# r4_4.net
KiCad netlist of a schematic drawn in EAGLE
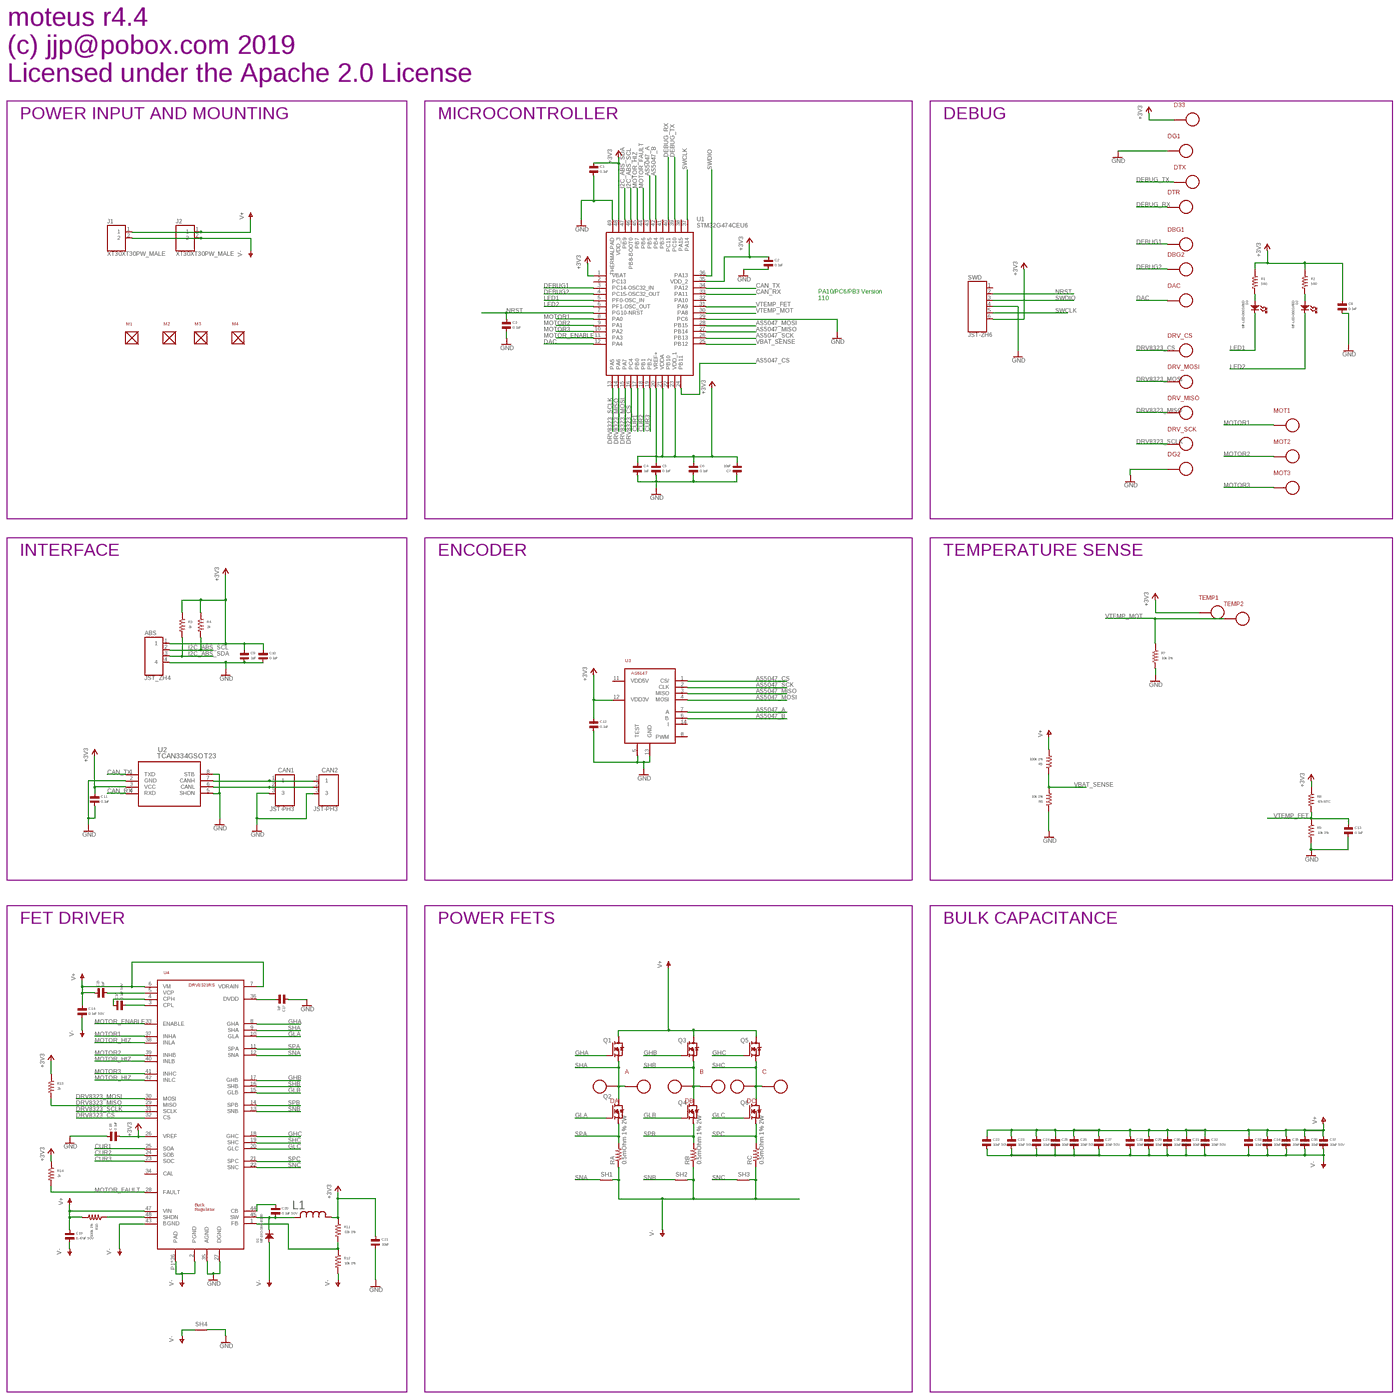
[diagram p0: schematic, sheet 1, overview]
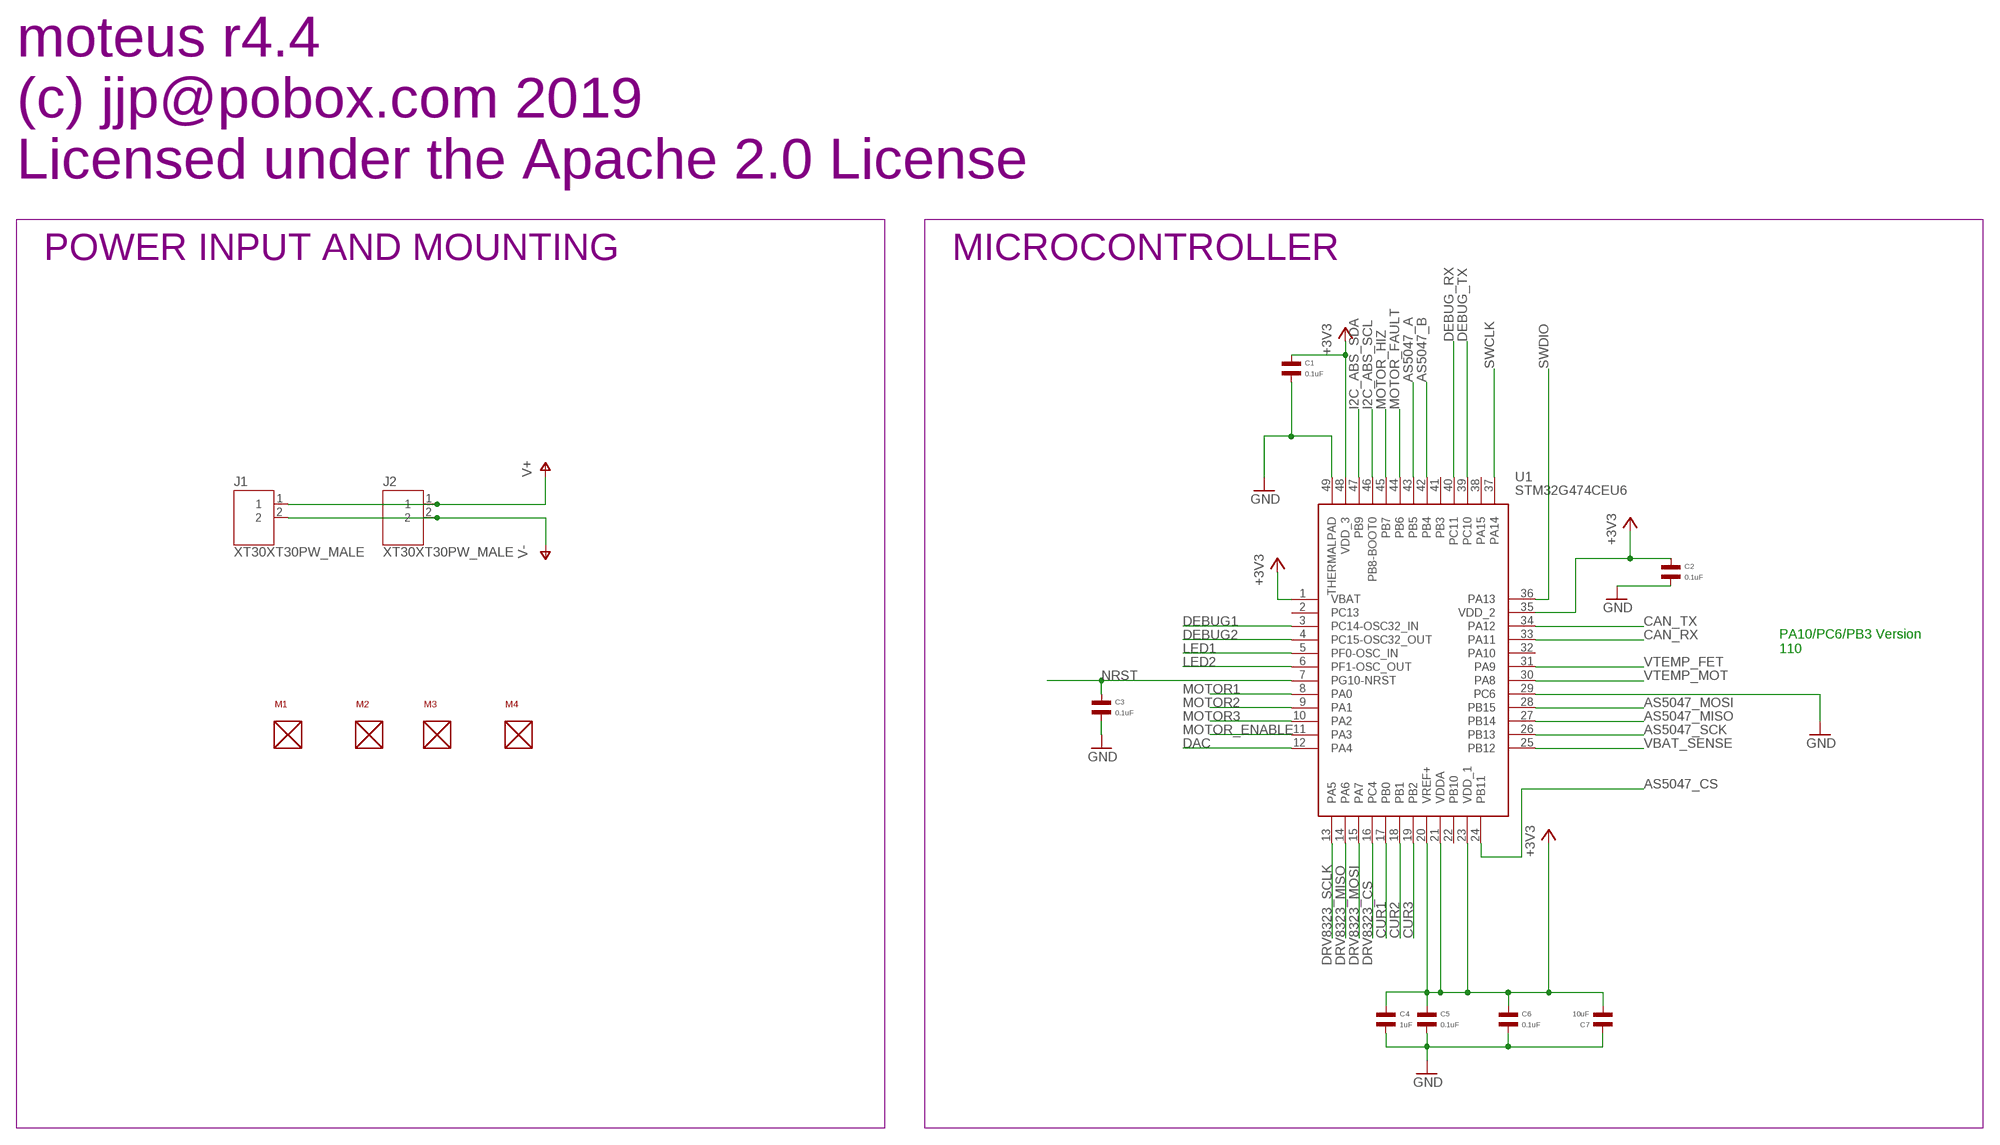
[diagram p1: schematic, sheet 1, part 1 of 4]
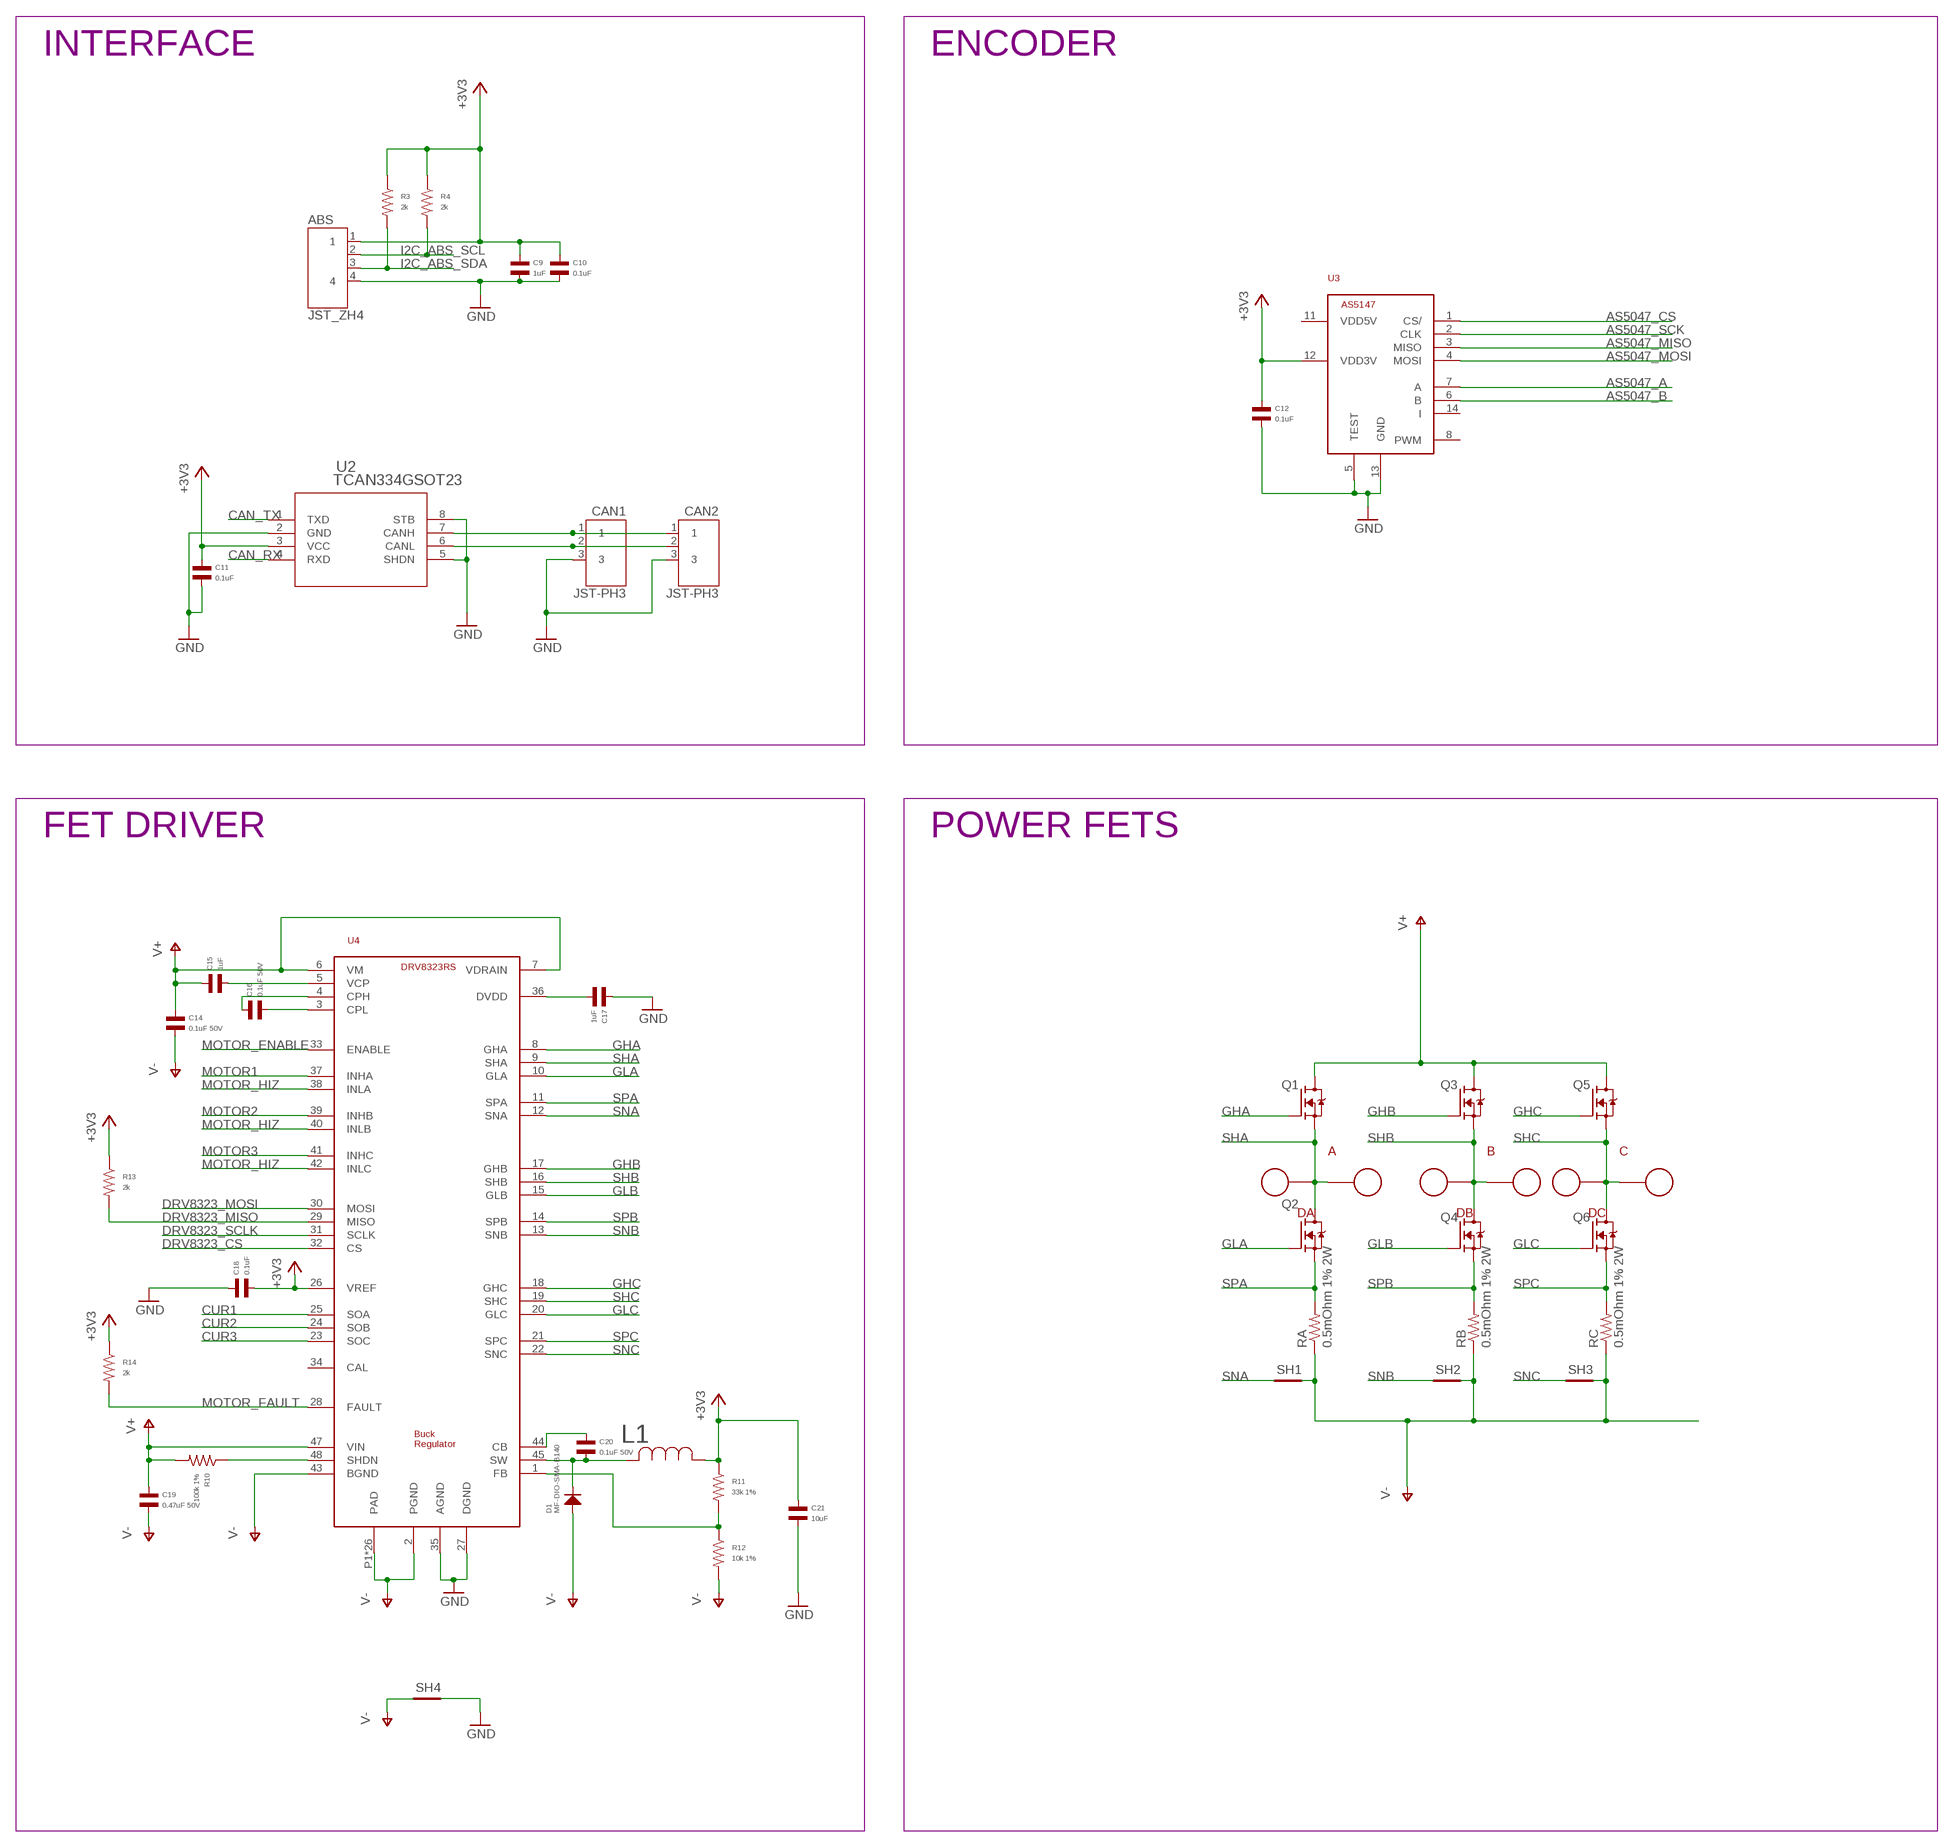
[diagram p2: schematic, sheet 1, part 2 of 4]
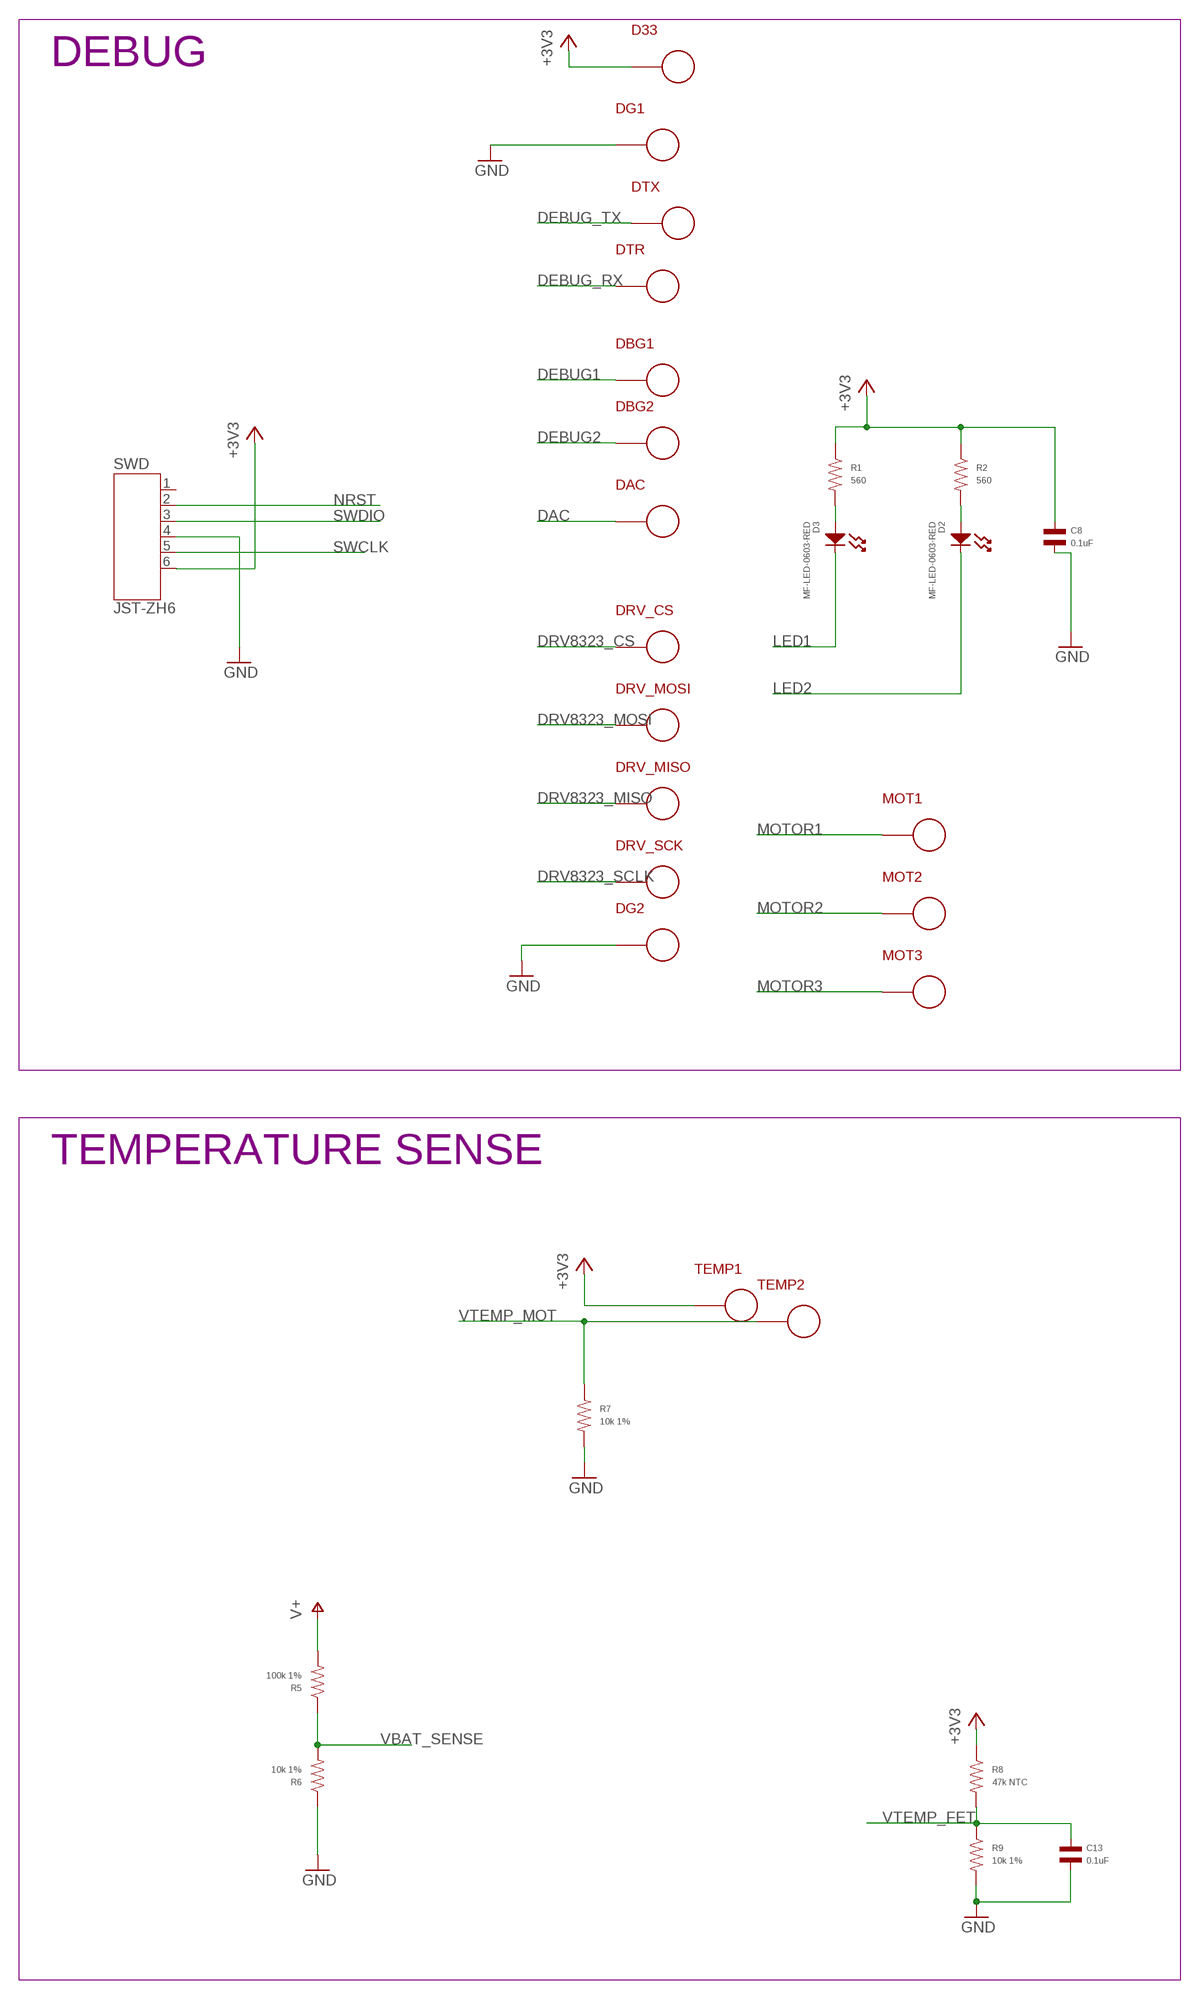
[diagram p3: schematic, sheet 1, part 3 of 4]
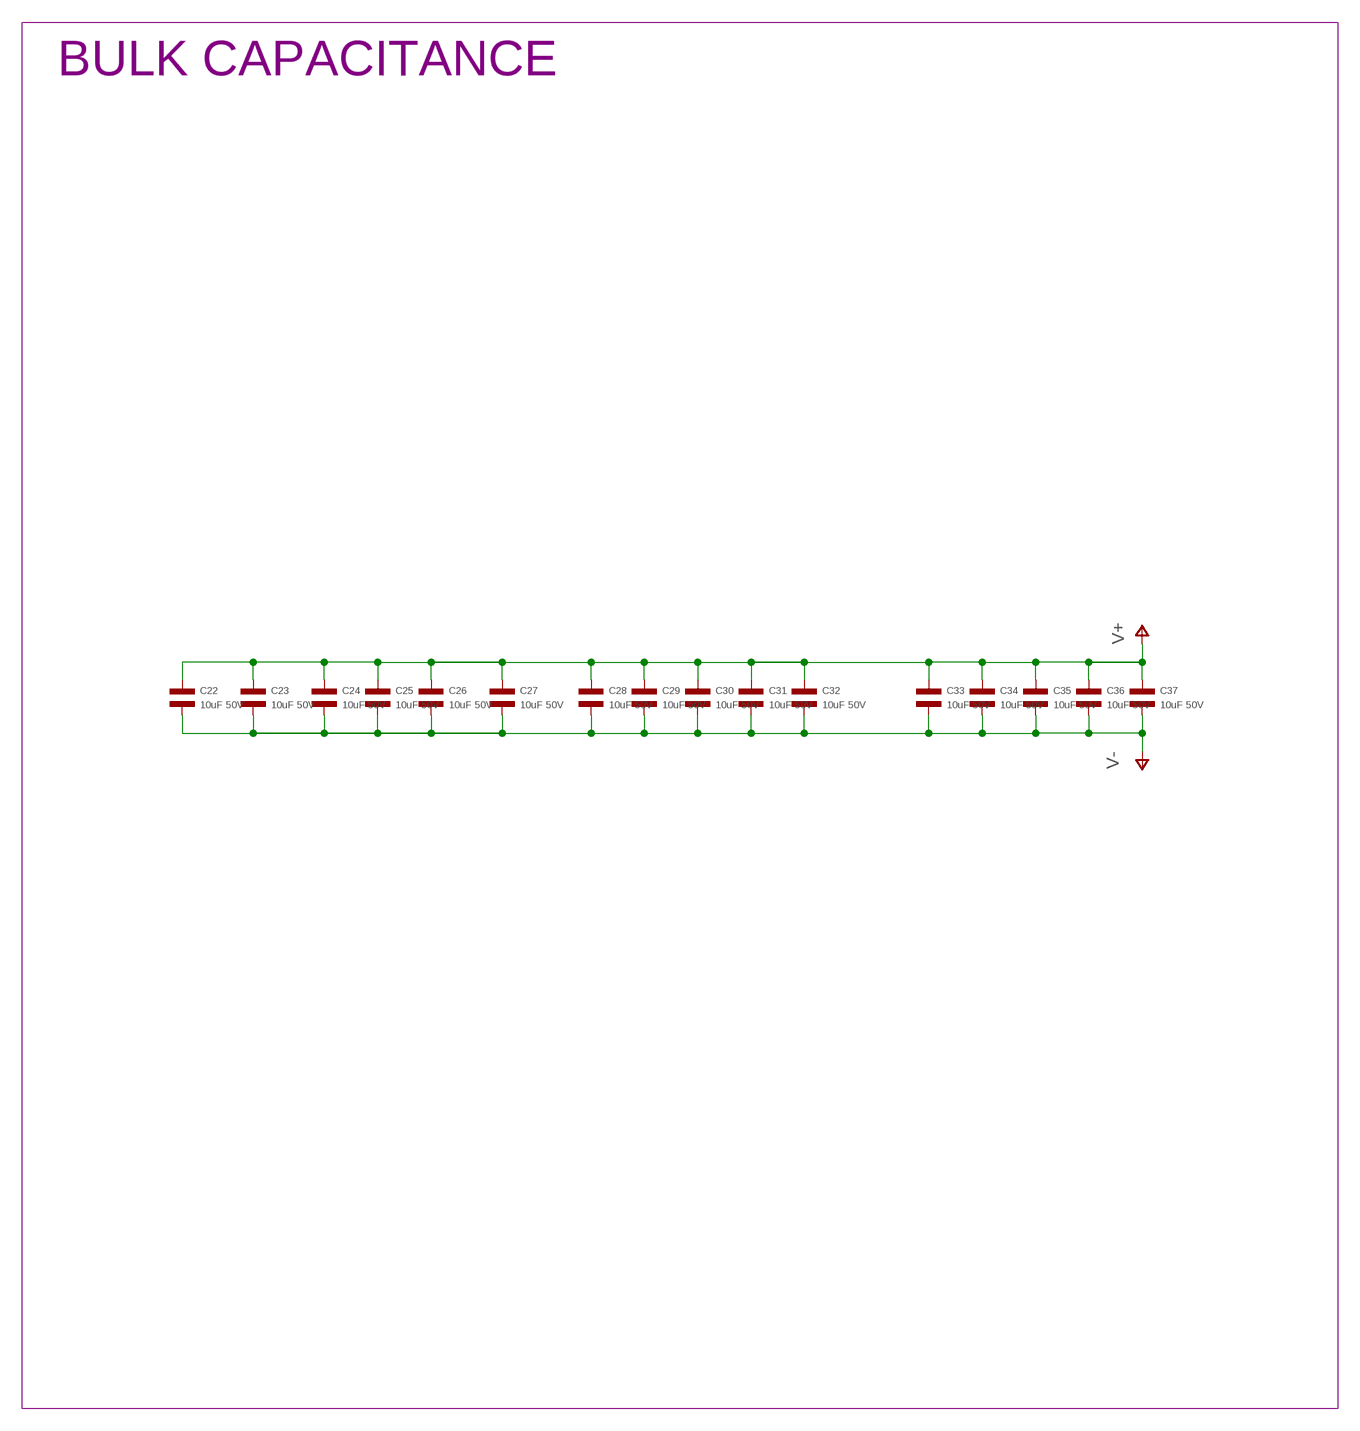
[diagram p4: schematic, sheet 1, part 4 of 4]

(export (version "E")
  (design (tool "Eeschema 10.0.6"))
  (components
    (comp (ref "A")
      (value "PAD")
      (footprint "eagle-import:18AWG_PAD")
      (libsource (lib "eagle-import") (part "PAD"))
    )
    (comp (ref "ABS")
      (value "JST_ZH4")
      (footprint "eagle-import:JST_S4B-ZR-SM4A-TF(LF)(SN)")
      (fields (field (name "MF") "JST") (field (name "MPN") "S4B-ZR-SM4A-TF(LF)(SN)"))
      (libsource (lib "eagle-import") (part "JST_ZH4"))
    )
    (comp (ref "B")
      (value "PAD")
      (footprint "eagle-import:18AWG_PAD")
      (libsource (lib "eagle-import") (part "PAD"))
    )
    (comp (ref "C")
      (value "PAD")
      (footprint "eagle-import:18AWG_PAD")
      (libsource (lib "eagle-import") (part "PAD"))
    )
    (comp (ref "C1")
      (value "0.1uF")
      (footprint "eagle-import:C0402")
      (fields (field (name "HOUSEPART") "YES") (field (name "MPN") "MF-CAP-0402-0.1uF"))
      (libsource (lib "eagle-import") (part "CAPACITOR_NP_0402"))
    )
    (comp (ref "C2")
      (value "0.1uF")
      (footprint "eagle-import:C0402")
      (fields (field (name "HOUSEPART") "YES") (field (name "MPN") "MF-CAP-0402-0.1uF"))
      (libsource (lib "eagle-import") (part "CAPACITOR_NP_0402"))
    )
    (comp (ref "C3")
      (value "0.1uF")
      (footprint "eagle-import:C0402")
      (fields (field (name "HOUSEPART") "YES") (field (name "MPN") "MF-CAP-0402-0.1uF"))
      (libsource (lib "eagle-import") (part "CAPACITOR_NP_0402"))
    )
    (comp (ref "C4")
      (value "1uF")
      (footprint "eagle-import:C0402")
      (fields (field (name "HOUSEPART") "YES") (field (name "MPN") "MF-CAP-0402-1uF"))
      (libsource (lib "eagle-import") (part "CAPACITOR_NP_0402"))
    )
    (comp (ref "C5")
      (value "0.1uF")
      (footprint "eagle-import:C0402")
      (fields (field (name "HOUSEPART") "YES") (field (name "MPN") "MF-CAP-0402-0.1uF"))
      (libsource (lib "eagle-import") (part "CAPACITOR_NP_0402"))
    )
    (comp (ref "C6")
      (value "0.1uF")
      (footprint "eagle-import:C0402")
      (fields (field (name "HOUSEPART") "YES") (field (name "MPN") "MF-CAP-0402-0.1uF"))
      (libsource (lib "eagle-import") (part "CAPACITOR_NP_0402"))
    )
    (comp (ref "C7")
      (value "10uF")
      (footprint "eagle-import:C1206")
      (fields (field (name "HOUSEPART") "YES") (field (name "MPN") "MF-CAP-1206-10uF"))
      (libsource (lib "eagle-import") (part "CAPACITOR_NP_1206"))
    )
    (comp (ref "C8")
      (value "0.1uF")
      (footprint "eagle-import:C0402")
      (fields (field (name "HOUSEPART") "YES") (field (name "MPN") "MF-CAP-0402-0.1uF"))
      (libsource (lib "eagle-import") (part "CAPACITOR_NP_0402"))
    )
    (comp (ref "C9")
      (value "1uF")
      (footprint "eagle-import:C0402")
      (fields (field (name "HOUSEPART") "YES") (field (name "MPN") "MF-CAP-0402-1uF"))
      (libsource (lib "eagle-import") (part "CAPACITOR_NP_0402"))
    )
    (comp (ref "C10")
      (value "0.1uF")
      (footprint "eagle-import:C0402")
      (fields (field (name "HOUSEPART") "YES") (field (name "MPN") "MF-CAP-0402-0.1uF"))
      (libsource (lib "eagle-import") (part "CAPACITOR_NP_0402"))
    )
    (comp (ref "C11")
      (value "0.1uF")
      (footprint "eagle-import:C0402")
      (fields (field (name "HOUSEPART") "YES") (field (name "MPN") "MF-CAP-0402-0.1uF"))
      (libsource (lib "eagle-import") (part "CAPACITOR_NP_0402"))
    )
    (comp (ref "C12")
      (value "0.1uF")
      (footprint "eagle-import:C0402")
      (fields (field (name "HOUSEPART") "YES") (field (name "MPN") "MF-CAP-0402-0.1uF"))
      (libsource (lib "eagle-import") (part "CAPACITOR_NP_0402"))
    )
    (comp (ref "C13")
      (value "0.1uF")
      (footprint "eagle-import:C0402")
      (fields (field (name "HOUSEPART") "YES") (field (name "MPN") "MF-CAP-0402-0.1uF"))
      (libsource (lib "eagle-import") (part "CAPACITOR_NP_0402"))
    )
    (comp (ref "C14")
      (value "0.1uF 50V")
      (footprint "eagle-import:C0402")
      (fields (field (name "MF") "TDK") (field (name "MPN") "CGA2B3X7R1H104K050BB"))
      (libsource (lib "eagle-import") (part "CAPACITOR_NP_0402"))
    )
    (comp (ref "C15")
      (value "1uF")
      (footprint "eagle-import:C0402")
      (fields (field (name "HOUSEPART") "YES") (field (name "MPN") "MF-CAP-0402-1uF"))
      (libsource (lib "eagle-import") (part "CAPACITOR_NP_0402"))
    )
    (comp (ref "C16")
      (value "0.1uF 50V")
      (footprint "eagle-import:C0402")
      (fields (field (name "MF") "TDK") (field (name "MPN") "CGA2B3X7R1H104K050BB"))
      (libsource (lib "eagle-import") (part "CAPACITOR_NP_0402"))
    )
    (comp (ref "C17")
      (value "1uF")
      (footprint "eagle-import:C0402")
      (fields (field (name "HOUSEPART") "YES") (field (name "MPN") "MF-CAP-0402-1uF"))
      (libsource (lib "eagle-import") (part "CAPACITOR_NP_0402"))
    )
    (comp (ref "C18")
      (value "0.1uF")
      (footprint "eagle-import:C0402")
      (fields (field (name "HOUSEPART") "YES") (field (name "MPN") "MF-CAP-0402-0.1uF"))
      (libsource (lib "eagle-import") (part "CAPACITOR_NP_0402"))
    )
    (comp (ref "C19")
      (value "0.47uF 50V")
      (footprint "eagle-import:C0402")
      (fields (field (name "MF") "Taiyo Yuden") (field (name "MPN") "UMK105ABJ474KV-F"))
      (libsource (lib "eagle-import") (part "CAPACITOR_NP_0402"))
    )
    (comp (ref "C20")
      (value "0.1uF 50V")
      (footprint "eagle-import:C0402")
      (fields (field (name "MF") "TDK") (field (name "MPN") "CGA2B3X7R1H104K050BB"))
      (libsource (lib "eagle-import") (part "CAPACITOR_NP_0402"))
    )
    (comp (ref "C21")
      (value "10uF")
      (footprint "eagle-import:C1206")
      (fields (field (name "HOUSEPART") "YES") (field (name "MPN") "MF-CAP-1206-10uF"))
      (libsource (lib "eagle-import") (part "CAPACITOR_NP_1206"))
    )
    (comp (ref "C22")
      (value "10uF 50V")
      (footprint "eagle-import:C1206")
      (fields (field (name "MF") "TDK") (field (name "MPN") "C3216X7R1H106K160AE"))
      (libsource (lib "eagle-import") (part "CAPACITOR_NP_1206"))
    )
    (comp (ref "C23")
      (value "10uF 50V")
      (footprint "eagle-import:C1206")
      (fields (field (name "MF") "TDK") (field (name "MPN") "C3216X7R1H106K160AE"))
      (libsource (lib "eagle-import") (part "CAPACITOR_NP_1206"))
    )
    (comp (ref "C24")
      (value "10uF 50V")
      (footprint "eagle-import:C1206")
      (fields (field (name "MF") "TDK") (field (name "MPN") "C3216X7R1H106K160AE"))
      (libsource (lib "eagle-import") (part "CAPACITOR_NP_1206"))
    )
    (comp (ref "C25")
      (value "10uF 50V")
      (footprint "eagle-import:C1206")
      (fields (field (name "MF") "TDK") (field (name "MPN") "C3216X7R1H106K160AE"))
      (libsource (lib "eagle-import") (part "CAPACITOR_NP_1206"))
    )
    (comp (ref "C26")
      (value "10uF 50V")
      (footprint "eagle-import:C1206")
      (fields (field (name "MF") "TDK") (field (name "MPN") "C3216X7R1H106K160AE"))
      (libsource (lib "eagle-import") (part "CAPACITOR_NP_1206"))
    )
    (comp (ref "C27")
      (value "10uF 50V")
      (footprint "eagle-import:C1206")
      (fields (field (name "MF") "TDK") (field (name "MPN") "C3216X7R1H106K160AE"))
      (libsource (lib "eagle-import") (part "CAPACITOR_NP_1206"))
    )
    (comp (ref "C28")
      (value "10uF 50V")
      (footprint "eagle-import:C1206")
      (fields (field (name "MF") "TDK") (field (name "MPN") "C3216X7R1H106K160AE"))
      (libsource (lib "eagle-import") (part "CAPACITOR_NP_1206"))
    )
    (comp (ref "C29")
      (value "10uF 50V")
      (footprint "eagle-import:C1206")
      (fields (field (name "MF") "TDK") (field (name "MPN") "C3216X7R1H106K160AE"))
      (libsource (lib "eagle-import") (part "CAPACITOR_NP_1206"))
    )
    (comp (ref "C30")
      (value "10uF 50V")
      (footprint "eagle-import:C1206")
      (fields (field (name "MF") "TDK") (field (name "MPN") "C3216X7R1H106K160AE"))
      (libsource (lib "eagle-import") (part "CAPACITOR_NP_1206"))
    )
    (comp (ref "C31")
      (value "10uF 50V")
      (footprint "eagle-import:C1206")
      (fields (field (name "MF") "TDK") (field (name "MPN") "C3216X7R1H106K160AE"))
      (libsource (lib "eagle-import") (part "CAPACITOR_NP_1206"))
    )
    (comp (ref "C32")
      (value "10uF 50V")
      (footprint "eagle-import:C1206")
      (fields (field (name "MF") "TDK") (field (name "MPN") "C3216X7R1H106K160AE"))
      (libsource (lib "eagle-import") (part "CAPACITOR_NP_1206"))
    )
    (comp (ref "C33")
      (value "10uF 50V")
      (footprint "eagle-import:C1206")
      (fields (field (name "MF") "TDK") (field (name "MPN") "C3216X7R1H106K160AE"))
      (libsource (lib "eagle-import") (part "CAPACITOR_NP_1206"))
    )
    (comp (ref "C34")
      (value "10uF 50V")
      (footprint "eagle-import:C1206")
      (fields (field (name "MF") "TDK") (field (name "MPN") "C3216X7R1H106K160AE"))
      (libsource (lib "eagle-import") (part "CAPACITOR_NP_1206"))
    )
    (comp (ref "C35")
      (value "10uF 50V")
      (footprint "eagle-import:C1206")
      (fields (field (name "MF") "TDK") (field (name "MPN") "C3216X7R1H106K160AE"))
      (libsource (lib "eagle-import") (part "CAPACITOR_NP_1206"))
    )
    (comp (ref "C36")
      (value "10uF 50V")
      (footprint "eagle-import:C1206")
      (fields (field (name "MF") "TDK") (field (name "MPN") "C3216X7R1H106K160AE"))
      (libsource (lib "eagle-import") (part "CAPACITOR_NP_1206"))
    )
    (comp (ref "C37")
      (value "10uF 50V")
      (footprint "eagle-import:C1206")
      (fields (field (name "MF") "TDK") (field (name "MPN") "C3216X7R1H106K160AE"))
      (libsource (lib "eagle-import") (part "CAPACITOR_NP_1206"))
    )
    (comp (ref "CAN1")
      (value "JST-PH3")
      (footprint "eagle-import:JST_S3B-PH-SM4-TB(LF)(SN)")
      (fields (field (name "MF") "JST") (field (name "MPN") "S3B-PH-SM4-TB(LF)(SN)"))
      (libsource (lib "eagle-import") (part "JST-PH3"))
    )
    (comp (ref "CAN2")
      (value "JST-PH3")
      (footprint "eagle-import:JST_S3B-PH-SM4-TB(LF)(SN)")
      (fields (field (name "MF") "JST") (field (name "MPN") "S3B-PH-SM4-TB(LF)(SN)"))
      (libsource (lib "eagle-import") (part "JST-PH3"))
    )
    (comp (ref "D1")
      (value "MF-DIO-SMA-B140")
      (footprint "eagle-import:SMA")
      (fields (field (name "HOUSEPART") "YES"))
      (libsource (lib "eagle-import") (part "DIODES_SMA_B140"))
    )
    (comp (ref "D2")
      (value "MF-LED-0603-RED")
      (footprint "eagle-import:LED0603")
      (fields (field (name "HOUSEPART") "YES") (field (name "MPN") "MF-LED-0603-GREEN"))
      (libsource (lib "eagle-import") (part "LED_SINGLE-0603-RED"))
    )
    (comp (ref "D3")
      (value "MF-LED-0603-RED")
      (footprint "eagle-import:LED0603")
      (fields (field (name "HOUSEPART") "YES"))
      (libsource (lib "eagle-import") (part "LED_SINGLE-0603-RED"))
    )
    (comp (ref "D33")
      (value "PAD24AWG_PAD")
      (footprint "eagle-import:24AWG_PAD")
      (libsource (lib "eagle-import") (part "PAD24AWG_PAD"))
    )
    (comp (ref "DA")
      (value "PAD24AWG_PAD")
      (footprint "eagle-import:24AWG_PAD")
      (libsource (lib "eagle-import") (part "PAD24AWG_PAD"))
    )
    (comp (ref "DAC")
      (value "PAD24AWG_PAD")
      (footprint "eagle-import:24AWG_PAD")
      (libsource (lib "eagle-import") (part "PAD24AWG_PAD"))
    )
    (comp (ref "DB")
      (value "PAD24AWG_PAD")
      (footprint "eagle-import:24AWG_PAD")
      (libsource (lib "eagle-import") (part "PAD24AWG_PAD"))
    )
    (comp (ref "DBG1")
      (value "PAD24AWG_PAD")
      (footprint "eagle-import:24AWG_PAD")
      (libsource (lib "eagle-import") (part "PAD24AWG_PAD"))
    )
    (comp (ref "DBG2")
      (value "PAD24AWG_PAD")
      (footprint "eagle-import:24AWG_PAD")
      (libsource (lib "eagle-import") (part "PAD24AWG_PAD"))
    )
    (comp (ref "DC")
      (value "PAD24AWG_PAD")
      (footprint "eagle-import:24AWG_PAD")
      (libsource (lib "eagle-import") (part "PAD24AWG_PAD"))
    )
    (comp (ref "DG1")
      (value "PAD24AWG_PAD")
      (footprint "eagle-import:24AWG_PAD")
      (libsource (lib "eagle-import") (part "PAD24AWG_PAD"))
    )
    (comp (ref "DG2")
      (value "PAD24AWG_PAD")
      (footprint "eagle-import:24AWG_PAD")
      (libsource (lib "eagle-import") (part "PAD24AWG_PAD"))
    )
    (comp (ref "DRV_CS")
      (value "PAD24AWG_PAD")
      (footprint "eagle-import:24AWG_PAD")
      (libsource (lib "eagle-import") (part "PAD24AWG_PAD"))
    )
    (comp (ref "DRV_MISO")
      (value "PAD24AWG_PAD")
      (footprint "eagle-import:24AWG_PAD")
      (libsource (lib "eagle-import") (part "PAD24AWG_PAD"))
    )
    (comp (ref "DRV_MOSI")
      (value "PAD24AWG_PAD")
      (footprint "eagle-import:24AWG_PAD")
      (libsource (lib "eagle-import") (part "PAD24AWG_PAD"))
    )
    (comp (ref "DRV_SCK")
      (value "PAD24AWG_PAD")
      (footprint "eagle-import:24AWG_PAD")
      (libsource (lib "eagle-import") (part "PAD24AWG_PAD"))
    )
    (comp (ref "DTR")
      (value "PAD24AWG_PAD")
      (footprint "eagle-import:24AWG_PAD")
      (libsource (lib "eagle-import") (part "PAD24AWG_PAD"))
    )
    (comp (ref "DTX")
      (value "PAD24AWG_PAD")
      (footprint "eagle-import:24AWG_PAD")
      (libsource (lib "eagle-import") (part "PAD24AWG_PAD"))
    )
    (comp (ref "J1")
      (value "XT30XT30PW_MALE")
      (footprint "eagle-import:XT30PW_MALE")
      (libsource (lib "eagle-import") (part "XT30XT30PW_MALE"))
    )
    (comp (ref "J2")
      (value "XT30XT30PW_MALE")
      (footprint "eagle-import:XT30PW_MALE")
      (libsource (lib "eagle-import") (part "XT30XT30PW_MALE"))
    )
    (comp (ref "L1")
      (value "SRN4018-220M")
      (footprint "eagle-import:IND_BOURNS_SRN4018")
      (fields (field (name "MANUFACTURER_PART_NUMBER") "SRN4018220M"))
      (libsource (lib "eagle-import") (part "SRN4018-220M"))
    )
    (comp (ref "M1")
      (value "MOUNT")
      (footprint "eagle-import:M2.5MOUNT")
      (libsource (lib "eagle-import") (part "MOUNT"))
    )
    (comp (ref "M2")
      (value "MOUNT")
      (footprint "eagle-import:M2.5MOUNT")
      (libsource (lib "eagle-import") (part "MOUNT"))
    )
    (comp (ref "M3")
      (value "MOUNT")
      (footprint "eagle-import:M2.5MOUNT")
      (libsource (lib "eagle-import") (part "MOUNT"))
    )
    (comp (ref "M4")
      (value "MOUNT")
      (footprint "eagle-import:M2.5MOUNT")
      (libsource (lib "eagle-import") (part "MOUNT"))
    )
    (comp (ref "MOT1")
      (value "PAD24AWG_PAD")
      (footprint "eagle-import:24AWG_PAD")
      (libsource (lib "eagle-import") (part "PAD24AWG_PAD"))
    )
    (comp (ref "MOT2")
      (value "PAD24AWG_PAD")
      (footprint "eagle-import:24AWG_PAD")
      (libsource (lib "eagle-import") (part "PAD24AWG_PAD"))
    )
    (comp (ref "MOT3")
      (value "PAD24AWG_PAD")
      (footprint "eagle-import:24AWG_PAD")
      (libsource (lib "eagle-import") (part "PAD24AWG_PAD"))
    )
    (comp (ref "Q1")
      (value "TPH1R204PLSOP_ADVANCE_8")
      (footprint "eagle-import:SOP_ADVANCE_8")
      (fields
        (field (name "MF") "Toshiba")
        (field (name "MPN") "TPH1R204PL")
        (field (name "MF_1") "Toshiba")
        (field (name "MPN_1") "TPH1R204PL,L1Q")
      )
      (libsource (lib "eagle-import") (part "TPH1R204PLSOP_ADVANCE_8"))
    )
    (comp (ref "Q2")
      (value "TPH1R204PLSOP_ADVANCE_8")
      (footprint "eagle-import:SOP_ADVANCE_8")
      (fields
        (field (name "MF") "Toshiba")
        (field (name "MPN") "TPH1R204PL")
        (field (name "MF_1") "Toshiba")
        (field (name "MPN_1") "TPH1R204PL,L1Q")
      )
      (libsource (lib "eagle-import") (part "TPH1R204PLSOP_ADVANCE_8"))
    )
    (comp (ref "Q3")
      (value "TPH1R204PLSOP_ADVANCE_8")
      (footprint "eagle-import:SOP_ADVANCE_8")
      (fields
        (field (name "MF") "Toshiba")
        (field (name "MPN") "TPH1R204PL")
        (field (name "MF_1") "Toshiba")
        (field (name "MPN_1") "TPH1R204PL,L1Q")
      )
      (libsource (lib "eagle-import") (part "TPH1R204PLSOP_ADVANCE_8"))
    )
    (comp (ref "Q4")
      (value "TPH1R204PLSOP_ADVANCE_8")
      (footprint "eagle-import:SOP_ADVANCE_8")
      (fields
        (field (name "MF") "Toshiba")
        (field (name "MPN") "TPH1R204PL")
        (field (name "MF_1") "Toshiba")
        (field (name "MPN_1") "TPH1R204PL,L1Q")
      )
      (libsource (lib "eagle-import") (part "TPH1R204PLSOP_ADVANCE_8"))
    )
    (comp (ref "Q5")
      (value "TPH1R204PLSOP_ADVANCE_8")
      (footprint "eagle-import:SOP_ADVANCE_8")
      (fields
        (field (name "MF") "Toshiba")
        (field (name "MPN") "TPH1R204PL")
        (field (name "MF_1") "Toshiba")
        (field (name "MPN_1") "TPH1R204PL,L1Q")
      )
      (libsource (lib "eagle-import") (part "TPH1R204PLSOP_ADVANCE_8"))
    )
    (comp (ref "Q6")
      (value "TPH1R204PLSOP_ADVANCE_8")
      (footprint "eagle-import:SOP_ADVANCE_8")
      (fields
        (field (name "MF") "Toshiba")
        (field (name "MPN") "TPH1R204PL")
        (field (name "MF_1") "Toshiba")
        (field (name "MPN_1") "TPH1R204PL,L1Q")
      )
      (libsource (lib "eagle-import") (part "TPH1R204PLSOP_ADVANCE_8"))
    )
    (comp (ref "R1")
      (value "560")
      (footprint "eagle-import:R0402")
      (fields (field (name "HOUSEPART") "1") (field (name "MPN") "MF-RES-0402-560"))
      (libsource (lib "eagle-import") (part "RESISTOR_0402"))
    )
    (comp (ref "R2")
      (value "560")
      (footprint "eagle-import:R0402")
      (fields (field (name "HOUSEPART") "1") (field (name "MPN") "MF-RES-0402-560"))
      (libsource (lib "eagle-import") (part "RESISTOR_0402"))
    )
    (comp (ref "R3")
      (value "2k")
      (footprint "eagle-import:R0402")
      (fields (field (name "HOUSEPART") "YES") (field (name "MPN") "MF-RES-0402-2K"))
      (libsource (lib "eagle-import") (part "RESISTOR_0402"))
    )
    (comp (ref "R4")
      (value "2k")
      (footprint "eagle-import:R0402")
      (fields (field (name "HOUSEPART") "YES") (field (name "MPN") "MF-RES-0402-2K"))
      (libsource (lib "eagle-import") (part "RESISTOR_0402"))
    )
    (comp (ref "R5")
      (value "100k 1%")
      (footprint "eagle-import:R0402")
      (fields (field (name "MF") "Panasonic") (field (name "MPN") "ERJ-2RKF1003X"))
      (libsource (lib "eagle-import") (part "RESISTOR_0402"))
    )
    (comp (ref "R6")
      (value "10k 1%")
      (footprint "eagle-import:R0402")
      (fields (field (name "MF") "Panasonic") (field (name "MPN") "ERJ-2RKF1002X"))
      (libsource (lib "eagle-import") (part "RESISTOR_0402"))
    )
    (comp (ref "R7")
      (value "10k 1%")
      (footprint "eagle-import:R0402")
      (fields (field (name "MF") "Panasonic") (field (name "MPN") "ERJ-2RKF1002X"))
      (libsource (lib "eagle-import") (part "RESISTOR_0402"))
    )
    (comp (ref "R8")
      (value "47k NTC")
      (footprint "eagle-import:R0402")
      (fields (field (name "MF") "Murata") (field (name "MPN") "NCP15WB473F03RC"))
      (libsource (lib "eagle-import") (part "RESISTOR_0402"))
    )
    (comp (ref "R9")
      (value "10k 1%")
      (footprint "eagle-import:R0402")
      (fields (field (name "MF") "Panasonic") (field (name "MPN") "ERJ-2RKF1002X"))
      (libsource (lib "eagle-import") (part "RESISTOR_0402"))
    )
    (comp (ref "R10")
      (value "100k 1%")
      (footprint "eagle-import:R0402")
      (fields (field (name "MF") "Panasonic") (field (name "MPN") "ERJ-2RKF1003X"))
      (libsource (lib "eagle-import") (part "RESISTOR_0402"))
    )
    (comp (ref "R11")
      (value "33k 1%")
      (footprint "eagle-import:R0402")
      (fields (field (name "MF") "Panasonic") (field (name "MPN") "ERJ-2RKF3302X"))
      (libsource (lib "eagle-import") (part "RESISTOR_0402"))
    )
    (comp (ref "R12")
      (value "10k 1%")
      (footprint "eagle-import:R0402")
      (fields (field (name "MF") "Panasonic") (field (name "MPN") "ERJ-2RKF1002X"))
      (libsource (lib "eagle-import") (part "RESISTOR_0402"))
    )
    (comp (ref "R13")
      (value "2k")
      (footprint "eagle-import:R0402")
      (fields (field (name "HOUSEPART") "YES") (field (name "MPN") "MF-RES-0402-2K"))
      (libsource (lib "eagle-import") (part "RESISTOR_0402"))
    )
    (comp (ref "R14")
      (value "2k")
      (footprint "eagle-import:R0402")
      (fields (field (name "HOUSEPART") "YES") (field (name "MPN") "MF-RES-0402-2K"))
      (libsource (lib "eagle-import") (part "RESISTOR_0402"))
    )
    (comp (ref "RA")
      (value "0.5mOhm 1% 2W")
      (footprint "eagle-import:M1206")
      (fields (field (name "MF") "Stackpole Electronics") (field (name "MPN") "HCS1206FTL500"))
      (libsource (lib "eagle-import") (part "R-US_M1206"))
    )
    (comp (ref "RB")
      (value "0.5mOhm 1% 2W")
      (footprint "eagle-import:M1206")
      (fields (field (name "MF") "Stackpole Electronics") (field (name "MPN") "HCS1206FTL500"))
      (libsource (lib "eagle-import") (part "R-US_M1206"))
    )
    (comp (ref "RC")
      (value "0.5mOhm 1% 2W")
      (footprint "eagle-import:M1206")
      (fields (field (name "MF") "Stackpole Electronics") (field (name "MPN") "HCS1206FTL500"))
      (libsource (lib "eagle-import") (part "R-US_M1206"))
    )
    (comp (ref "SH1")
      (value "SHORTT5")
      (footprint "eagle-import:SHORT_TOP-50")
      (libsource (lib "eagle-import") (part "SHORTT5"))
    )
    (comp (ref "SH2")
      (value "SHORTT5")
      (footprint "eagle-import:SHORT_TOP-50")
      (libsource (lib "eagle-import") (part "SHORTT5"))
    )
    (comp (ref "SH3")
      (value "SHORTT5")
      (footprint "eagle-import:SHORT_TOP-50")
      (libsource (lib "eagle-import") (part "SHORTT5"))
    )
    (comp (ref "SH4")
      (value "SHORTBIG")
      (footprint "eagle-import:SHORT_TOP-BIG")
      (libsource (lib "eagle-import") (part "SHORTBIG"))
    )
    (comp (ref "SWD")
      (value "JST-ZH6")
      (footprint "eagle-import:JST_S6B-ZR-SM4A-TF(LF)(SN)")
      (fields (field (name "MF") "JST") (field (name "MPN") "S6B-ZR-SM4A-TF(LF)(SN)"))
      (libsource (lib "eagle-import") (part "JST-ZH6"))
    )
    (comp (ref "TEMP1")
      (value "PAD24AWG_PAD")
      (footprint "eagle-import:24AWG_PAD")
      (libsource (lib "eagle-import") (part "PAD24AWG_PAD"))
    )
    (comp (ref "TEMP2")
      (value "PAD24AWG_PAD")
      (footprint "eagle-import:24AWG_PAD")
      (libsource (lib "eagle-import") (part "PAD24AWG_PAD"))
    )
    (comp (ref "U1")
      (value "STM32G474CEU6")
      (footprint "eagle-import:QFN50P700X700X60-49N")
      (fields (field (name "MOUSER_PART_NUMBER") "511-STM32G474CEU6"))
      (libsource (lib "eagle-import") (part "STM32G474CEU6"))
    )
    (comp (ref "U2")
      (value "TCAN334GSOT23")
      (footprint "eagle-import:SOT23-8")
      (fields (field (name "MF") "TI") (field (name "MPN") "TCAN334GDCNT"))
      (libsource (lib "eagle-import") (part "TCAN334GSOT23"))
    )
    (comp (ref "U3")
      (value "AS5147")
      (footprint "eagle-import:TSSOP14")
      (fields (field (name "MF") "AMS") (field (name "MPN") "AS5047P-ATSM"))
      (libsource (lib "eagle-import") (part "AS5147"))
    )
    (comp (ref "U4")
      (value "DRV8323RS")
      (footprint "eagle-import:PVQFN-N48")
      (fields (field (name "MF") "TI") (field (name "MPN") "DRV8323RSRGZR"))
      (libsource (lib "eagle-import") (part "DRV8323RS"))
    )
  )
  (nets
    (net (code "1") (name "+3V3") (class "Default")
      (node (ref "ABS") (pin "1") (pinfunction "1_1") (pintype "passive"))
      (node (ref "C1") (pin "P$1") (pinfunction "P$1_P$1") (pintype "passive"))
      (node (ref "C10") (pin "P$1") (pinfunction "P$1_P$1") (pintype "passive"))
      (node (ref "C11") (pin "P$1") (pinfunction "P$1_P$1") (pintype "passive"))
      (node (ref "C12") (pin "P$1") (pinfunction "P$1_P$1") (pintype "passive"))
      (node (ref "C18") (pin "P$2") (pinfunction "P$2_P$2") (pintype "passive"))
      (node (ref "C2") (pin "P$1") (pinfunction "P$1_P$1") (pintype "passive"))
      (node (ref "C21") (pin "P$1") (pinfunction "P$1_P$1") (pintype "passive"))
      (node (ref "C4") (pin "P$1") (pinfunction "P$1_P$1") (pintype "passive"))
      (node (ref "C5") (pin "P$1") (pinfunction "P$1_P$1") (pintype "passive"))
      (node (ref "C6") (pin "P$1") (pinfunction "P$1_P$1") (pintype "passive"))
      (node (ref "C7") (pin "P$2") (pinfunction "P$2_P$2") (pintype "passive"))
      (node (ref "C8") (pin "P$1") (pinfunction "P$1_P$1") (pintype "passive"))
      (node (ref "C9") (pin "P$1") (pinfunction "P$1_P$1") (pintype "passive"))
      (node (ref "D33") (pin "P$1") (pinfunction "P$1_P$1") (pintype "bidirectional"))
      (node (ref "L1") (pin "1") (pinfunction "1_1") (pintype "passive"))
      (node (ref "R1") (pin "P$1") (pinfunction "P$1_P$1") (pintype "passive"))
      (node (ref "R11") (pin "P$1") (pinfunction "P$1_P$1") (pintype "passive"))
      (node (ref "R13") (pin "P$1") (pinfunction "P$1_P$1") (pintype "passive"))
      (node (ref "R14") (pin "P$1") (pinfunction "P$1_P$1") (pintype "passive"))
      (node (ref "R2") (pin "P$1") (pinfunction "P$1_P$1") (pintype "passive"))
      (node (ref "R3") (pin "P$1") (pinfunction "P$1_P$1") (pintype "passive"))
      (node (ref "R4") (pin "P$1") (pinfunction "P$1_P$1") (pintype "passive"))
      (node (ref "R8") (pin "P$1") (pinfunction "P$1_P$1") (pintype "passive"))
      (node (ref "SWD") (pin "6") (pinfunction "6_6") (pintype "passive"))
      (node (ref "TEMP1") (pin "P$1") (pinfunction "P$1_P$1") (pintype "bidirectional"))
      (node (ref "U1") (pin "1") (pinfunction "VBAT_1") (pintype "bidirectional"))
      (node (ref "U1") (pin "20") (pinfunction "VREF+_20") (pintype "bidirectional"))
      (node (ref "U1") (pin "21") (pinfunction "VDDA_21") (pintype "bidirectional"))
      (node (ref "U1") (pin "23") (pinfunction "VDD_1_23") (pintype "bidirectional"))
      (node (ref "U1") (pin "35") (pinfunction "VDD_2_35") (pintype "bidirectional"))
      (node (ref "U1") (pin "48") (pinfunction "VDD_3_48") (pintype "bidirectional"))
      (node (ref "U2") (pin "3") (pinfunction "VCC_3") (pintype "power_in"))
      (node (ref "U3") (pin "12") (pinfunction "VDD3V_12") (pintype "bidirectional"))
      (node (ref "U4") (pin "26") (pinfunction "VREF_26") (pintype "bidirectional"))
    )
    (net (code "2") (name "/AS5047_A") (class "Default")
      (node (ref "U1") (pin "43") (pinfunction "PB5_43") (pintype "bidirectional"))
      (node (ref "U3") (pin "7") (pinfunction "A_7") (pintype "bidirectional"))
    )
    (net (code "3") (name "/AS5047_B") (class "Default")
      (node (ref "U1") (pin "42") (pinfunction "PB4_42") (pintype "bidirectional"))
      (node (ref "U3") (pin "6") (pinfunction "B_6") (pintype "bidirectional"))
    )
    (net (code "4") (name "/AS5047_CS") (class "Default")
      (node (ref "U1") (pin "24") (pinfunction "PB11_24") (pintype "bidirectional"))
      (node (ref "U3") (pin "1") (pinfunction "CS/_1") (pintype "bidirectional"))
    )
    (net (code "5") (name "/AS5047_MISO") (class "Default")
      (node (ref "U1") (pin "27") (pinfunction "PB14_27") (pintype "bidirectional"))
      (node (ref "U3") (pin "3") (pinfunction "MISO_3") (pintype "bidirectional"))
    )
    (net (code "6") (name "/AS5047_MOSI") (class "Default")
      (node (ref "U1") (pin "28") (pinfunction "PB15_28") (pintype "bidirectional"))
      (node (ref "U3") (pin "4") (pinfunction "MOSI_4") (pintype "bidirectional"))
    )
    (net (code "7") (name "/AS5047_SCK") (class "Default")
      (node (ref "U1") (pin "26") (pinfunction "PB13_26") (pintype "bidirectional"))
      (node (ref "U3") (pin "2") (pinfunction "CLK_2") (pintype "bidirectional"))
    )
    (net (code "8") (name "/CAN_RX") (class "Default")
      (node (ref "U1") (pin "33") (pinfunction "PA11_33") (pintype "bidirectional"))
      (node (ref "U2") (pin "4") (pinfunction "RXD_4") (pintype "output"))
    )
    (net (code "9") (name "/CAN_TX") (class "Default")
      (node (ref "U1") (pin "34") (pinfunction "PA12_34") (pintype "bidirectional"))
      (node (ref "U2") (pin "1") (pinfunction "TXD_1") (pintype "input"))
    )
    (net (code "10") (name "/CUR1") (class "Default")
      (node (ref "U1") (pin "17") (pinfunction "PB0_17") (pintype "bidirectional"))
      (node (ref "U4") (pin "25") (pinfunction "SOA_25") (pintype "bidirectional"))
    )
    (net (code "11") (name "/CUR2") (class "Default")
      (node (ref "U1") (pin "18") (pinfunction "PB1_18") (pintype "bidirectional"))
      (node (ref "U4") (pin "24") (pinfunction "SOB_24") (pintype "bidirectional"))
    )
    (net (code "12") (name "/CUR3") (class "Default")
      (node (ref "U1") (pin "19") (pinfunction "PB2_19") (pintype "bidirectional"))
      (node (ref "U4") (pin "23") (pinfunction "SOC_23") (pintype "bidirectional"))
    )
    (net (code "13") (name "/DAC") (class "Default")
      (node (ref "DAC") (pin "P$1") (pinfunction "P$1_P$1") (pintype "bidirectional"))
      (node (ref "U1") (pin "12") (pinfunction "PA4_12") (pintype "bidirectional"))
    )
    (net (code "14") (name "/DEBUG1") (class "Default")
      (node (ref "DBG1") (pin "P$1") (pinfunction "P$1_P$1") (pintype "bidirectional"))
      (node (ref "U1") (pin "3") (pinfunction "PC14-OSC32_IN_3") (pintype "bidirectional"))
    )
    (net (code "15") (name "/DEBUG2") (class "Default")
      (node (ref "DBG2") (pin "P$1") (pinfunction "P$1_P$1") (pintype "bidirectional"))
      (node (ref "U1") (pin "4") (pinfunction "PC15-OSC32_OUT_4") (pintype "bidirectional"))
    )
    (net (code "16") (name "/DEBUG_RX") (class "Default")
      (node (ref "DTR") (pin "P$1") (pinfunction "P$1_P$1") (pintype "bidirectional"))
      (node (ref "U1") (pin "40") (pinfunction "PC11_40") (pintype "bidirectional"))
    )
    (net (code "17") (name "/DEBUG_TX") (class "Default")
      (node (ref "DTX") (pin "P$1") (pinfunction "P$1_P$1") (pintype "bidirectional"))
      (node (ref "U1") (pin "39") (pinfunction "PC10_39") (pintype "bidirectional"))
    )
    (net (code "18") (name "/DRV8323_CS") (class "Default")
      (node (ref "DRV_CS") (pin "P$1") (pinfunction "P$1_P$1") (pintype "bidirectional"))
      (node (ref "U1") (pin "16") (pinfunction "PC4_16") (pintype "bidirectional"))
      (node (ref "U4") (pin "32") (pinfunction "CS_32") (pintype "bidirectional"))
    )
    (net (code "19") (name "/DRV8323_MISO") (class "Default")
      (node (ref "DRV_MISO") (pin "P$1") (pinfunction "P$1_P$1") (pintype "bidirectional"))
      (node (ref "R13") (pin "P$2") (pinfunction "P$2_P$2") (pintype "passive"))
      (node (ref "U1") (pin "14") (pinfunction "PA6_14") (pintype "bidirectional"))
      (node (ref "U4") (pin "29") (pinfunction "MISO_29") (pintype "bidirectional"))
    )
    (net (code "20") (name "/DRV8323_MOSI") (class "Default")
      (node (ref "DRV_MOSI") (pin "P$1") (pinfunction "P$1_P$1") (pintype "bidirectional"))
      (node (ref "U1") (pin "15") (pinfunction "PA7_15") (pintype "bidirectional"))
      (node (ref "U4") (pin "30") (pinfunction "MOSI_30") (pintype "bidirectional"))
    )
    (net (code "21") (name "/DRV8323_SCLK") (class "Default")
      (node (ref "DRV_SCK") (pin "P$1") (pinfunction "P$1_P$1") (pintype "bidirectional"))
      (node (ref "U1") (pin "13") (pinfunction "PA5_13") (pintype "bidirectional"))
      (node (ref "U4") (pin "31") (pinfunction "SCLK_31") (pintype "bidirectional"))
    )
    (net (code "22") (name "/GHA") (class "Default")
      (node (ref "Q1") (pin "4") (pinfunction "G_4") (pintype "passive"))
      (node (ref "U4") (pin "8") (pinfunction "GHA_8") (pintype "bidirectional"))
    )
    (net (code "23") (name "/GHB") (class "Default")
      (node (ref "Q3") (pin "4") (pinfunction "G_4") (pintype "passive"))
      (node (ref "U4") (pin "17") (pinfunction "GHB_17") (pintype "bidirectional"))
    )
    (net (code "24") (name "/GHC") (class "Default")
      (node (ref "Q5") (pin "4") (pinfunction "G_4") (pintype "passive"))
      (node (ref "U4") (pin "18") (pinfunction "GHC_18") (pintype "bidirectional"))
    )
    (net (code "25") (name "/GLA") (class "Default")
      (node (ref "Q2") (pin "4") (pinfunction "G_4") (pintype "passive"))
      (node (ref "U4") (pin "10") (pinfunction "GLA_10") (pintype "bidirectional"))
    )
    (net (code "26") (name "/GLB") (class "Default")
      (node (ref "Q4") (pin "4") (pinfunction "G_4") (pintype "passive"))
      (node (ref "U4") (pin "15") (pinfunction "GLB_15") (pintype "bidirectional"))
    )
    (net (code "27") (name "/GLC") (class "Default")
      (node (ref "Q6") (pin "4") (pinfunction "G_4") (pintype "passive"))
      (node (ref "U4") (pin "20") (pinfunction "GLC_20") (pintype "bidirectional"))
    )
    (net (code "28") (name "/I2C_ABS_SCL") (class "Default")
      (node (ref "ABS") (pin "2") (pinfunction "2_2") (pintype "passive"))
      (node (ref "R4") (pin "P$2") (pinfunction "P$2_P$2") (pintype "passive"))
      (node (ref "U1") (pin "46") (pinfunction "PB8-BOOT0_46") (pintype "bidirectional"))
    )
    (net (code "29") (name "/I2C_ABS_SDA") (class "Default")
      (node (ref "ABS") (pin "3") (pinfunction "3_3") (pintype "passive"))
      (node (ref "R3") (pin "P$2") (pinfunction "P$2_P$2") (pintype "passive"))
      (node (ref "U1") (pin "47") (pinfunction "PB9_47") (pintype "bidirectional"))
    )
    (net (code "30") (name "/LED1") (class "Default")
      (node (ref "D3") (pin "CATHODE") (pinfunction "CATHODE_CATHODE") (pintype "power_in"))
      (node (ref "U1") (pin "5") (pinfunction "PF0-OSC_IN_5") (pintype "bidirectional"))
    )
    (net (code "31") (name "/LED2") (class "Default")
      (node (ref "D2") (pin "CATHODE") (pinfunction "CATHODE_CATHODE") (pintype "power_in"))
      (node (ref "U1") (pin "6") (pinfunction "PF1-OSC_OUT_6") (pintype "bidirectional"))
    )
    (net (code "32") (name "/MOTOR1") (class "Default")
      (node (ref "MOT1") (pin "P$1") (pinfunction "P$1_P$1") (pintype "bidirectional"))
      (node (ref "U1") (pin "8") (pinfunction "PA0_8") (pintype "bidirectional"))
      (node (ref "U4") (pin "37") (pinfunction "INHA_37") (pintype "bidirectional"))
    )
    (net (code "33") (name "/MOTOR2") (class "Default")
      (node (ref "MOT2") (pin "P$1") (pinfunction "P$1_P$1") (pintype "bidirectional"))
      (node (ref "U1") (pin "9") (pinfunction "PA1_9") (pintype "bidirectional"))
      (node (ref "U4") (pin "39") (pinfunction "INHB_39") (pintype "bidirectional"))
    )
    (net (code "34") (name "/MOTOR3") (class "Default")
      (node (ref "MOT3") (pin "P$1") (pinfunction "P$1_P$1") (pintype "bidirectional"))
      (node (ref "U1") (pin "10") (pinfunction "PA2_10") (pintype "bidirectional"))
      (node (ref "U4") (pin "41") (pinfunction "INHC_41") (pintype "bidirectional"))
    )
    (net (code "35") (name "/MOTOR_ENABLE") (class "Default")
      (node (ref "U1") (pin "11") (pinfunction "PA3_11") (pintype "bidirectional"))
      (node (ref "U4") (pin "33") (pinfunction "ENABLE_33") (pintype "bidirectional"))
    )
    (net (code "36") (name "/MOTOR_FAULT") (class "Default")
      (node (ref "R14") (pin "P$2") (pinfunction "P$2_P$2") (pintype "passive"))
      (node (ref "U1") (pin "44") (pinfunction "PB6_44") (pintype "bidirectional"))
      (node (ref "U4") (pin "28") (pinfunction "FAULT_28") (pintype "bidirectional"))
    )
    (net (code "37") (name "/MOTOR_HIZ") (class "Default")
      (node (ref "U1") (pin "45") (pinfunction "PB7_45") (pintype "bidirectional"))
      (node (ref "U4") (pin "38") (pinfunction "INLA_38") (pintype "bidirectional"))
      (node (ref "U4") (pin "40") (pinfunction "INLB_40") (pintype "bidirectional"))
      (node (ref "U4") (pin "42") (pinfunction "INLC_42") (pintype "bidirectional"))
    )
    (net (code "38") (name "/NRST") (class "Default")
      (node (ref "C3") (pin "P$1") (pinfunction "P$1_P$1") (pintype "passive"))
      (node (ref "SWD") (pin "2") (pinfunction "2_2") (pintype "passive"))
      (node (ref "U1") (pin "7") (pinfunction "PG10-NRST_7") (pintype "bidirectional"))
    )
    (net (code "39") (name "/SHA") (class "Default")
      (node (ref "A") (pin "1") (pinfunction "P$1_1") (pintype "bidirectional"))
      (node (ref "DA") (pin "P$1") (pinfunction "P$1_P$1") (pintype "bidirectional"))
      (node (ref "Q1") (pin "1") (pinfunction "S_1") (pintype "passive"))
      (node (ref "Q1") (pin "2") (pinfunction "S_2") (pintype "passive"))
      (node (ref "Q1") (pin "3") (pinfunction "S_3") (pintype "passive"))
      (node (ref "Q2") (pin "5") (pinfunction "D_5") (pintype "passive"))
      (node (ref "Q2") (pin "6") (pinfunction "D_6") (pintype "passive"))
      (node (ref "Q2") (pin "7") (pinfunction "D_7") (pintype "passive"))
      (node (ref "Q2") (pin "8") (pinfunction "D_8") (pintype "passive"))
      (node (ref "Q2") (pin "PAD") (pinfunction "D_PAD") (pintype "passive"))
      (node (ref "U4") (pin "9") (pinfunction "SHA_9") (pintype "bidirectional"))
    )
    (net (code "40") (name "/SHB") (class "Default")
      (node (ref "B") (pin "1") (pinfunction "P$1_1") (pintype "bidirectional"))
      (node (ref "DB") (pin "P$1") (pinfunction "P$1_P$1") (pintype "bidirectional"))
      (node (ref "Q3") (pin "1") (pinfunction "S_1") (pintype "passive"))
      (node (ref "Q3") (pin "2") (pinfunction "S_2") (pintype "passive"))
      (node (ref "Q3") (pin "3") (pinfunction "S_3") (pintype "passive"))
      (node (ref "Q4") (pin "5") (pinfunction "D_5") (pintype "passive"))
      (node (ref "Q4") (pin "6") (pinfunction "D_6") (pintype "passive"))
      (node (ref "Q4") (pin "7") (pinfunction "D_7") (pintype "passive"))
      (node (ref "Q4") (pin "8") (pinfunction "D_8") (pintype "passive"))
      (node (ref "Q4") (pin "PAD") (pinfunction "D_PAD") (pintype "passive"))
      (node (ref "U4") (pin "16") (pinfunction "SHB_16") (pintype "bidirectional"))
    )
    (net (code "41") (name "/SHC") (class "Default")
      (node (ref "C") (pin "1") (pinfunction "P$1_1") (pintype "bidirectional"))
      (node (ref "DC") (pin "P$1") (pinfunction "P$1_P$1") (pintype "bidirectional"))
      (node (ref "Q5") (pin "1") (pinfunction "S_1") (pintype "passive"))
      (node (ref "Q5") (pin "2") (pinfunction "S_2") (pintype "passive"))
      (node (ref "Q5") (pin "3") (pinfunction "S_3") (pintype "passive"))
      (node (ref "Q6") (pin "5") (pinfunction "D_5") (pintype "passive"))
      (node (ref "Q6") (pin "6") (pinfunction "D_6") (pintype "passive"))
      (node (ref "Q6") (pin "7") (pinfunction "D_7") (pintype "passive"))
      (node (ref "Q6") (pin "8") (pinfunction "D_8") (pintype "passive"))
      (node (ref "Q6") (pin "PAD") (pinfunction "D_PAD") (pintype "passive"))
      (node (ref "U4") (pin "19") (pinfunction "SHC_19") (pintype "bidirectional"))
    )
    (net (code "42") (name "/SNA") (class "Default")
      (node (ref "SH1") (pin "1") (pinfunction "P$1_1") (pintype "bidirectional"))
      (node (ref "U4") (pin "12") (pinfunction "SNA_12") (pintype "bidirectional"))
    )
    (net (code "43") (name "/SNB") (class "Default")
      (node (ref "SH2") (pin "1") (pinfunction "P$1_1") (pintype "bidirectional"))
      (node (ref "U4") (pin "13") (pinfunction "SNB_13") (pintype "bidirectional"))
    )
    (net (code "44") (name "/SNC") (class "Default")
      (node (ref "SH3") (pin "1") (pinfunction "P$1_1") (pintype "bidirectional"))
      (node (ref "U4") (pin "22") (pinfunction "SNC_22") (pintype "bidirectional"))
    )
    (net (code "45") (name "/SPA") (class "Default")
      (node (ref "Q2") (pin "1") (pinfunction "S_1") (pintype "passive"))
      (node (ref "Q2") (pin "2") (pinfunction "S_2") (pintype "passive"))
      (node (ref "Q2") (pin "3") (pinfunction "S_3") (pintype "passive"))
      (node (ref "RA") (pin "2") (pinfunction "2_2") (pintype "passive"))
      (node (ref "U4") (pin "11") (pinfunction "SPA_11") (pintype "bidirectional"))
    )
    (net (code "46") (name "/SPB") (class "Default")
      (node (ref "Q4") (pin "1") (pinfunction "S_1") (pintype "passive"))
      (node (ref "Q4") (pin "2") (pinfunction "S_2") (pintype "passive"))
      (node (ref "Q4") (pin "3") (pinfunction "S_3") (pintype "passive"))
      (node (ref "RB") (pin "2") (pinfunction "2_2") (pintype "passive"))
      (node (ref "U4") (pin "14") (pinfunction "SPB_14") (pintype "bidirectional"))
    )
    (net (code "47") (name "/SPC") (class "Default")
      (node (ref "Q6") (pin "1") (pinfunction "S_1") (pintype "passive"))
      (node (ref "Q6") (pin "2") (pinfunction "S_2") (pintype "passive"))
      (node (ref "Q6") (pin "3") (pinfunction "S_3") (pintype "passive"))
      (node (ref "RC") (pin "2") (pinfunction "2_2") (pintype "passive"))
      (node (ref "U4") (pin "21") (pinfunction "SPC_21") (pintype "bidirectional"))
    )
    (net (code "48") (name "/SWCLK") (class "Default")
      (node (ref "SWD") (pin "5") (pinfunction "5_5") (pintype "passive"))
      (node (ref "U1") (pin "37") (pinfunction "PA14_37") (pintype "bidirectional"))
    )
    (net (code "49") (name "/SWDIO") (class "Default")
      (node (ref "SWD") (pin "3") (pinfunction "3_3") (pintype "passive"))
      (node (ref "U1") (pin "36") (pinfunction "PA13_36") (pintype "bidirectional"))
    )
    (net (code "50") (name "/VBAT_SENSE") (class "Default")
      (node (ref "R5") (pin "P$1") (pinfunction "P$1_P$1") (pintype "passive"))
      (node (ref "R6") (pin "P$2") (pinfunction "P$2_P$2") (pintype "passive"))
      (node (ref "U1") (pin "25") (pinfunction "PB12_25") (pintype "bidirectional"))
    )
    (net (code "51") (name "/VTEMP_FET") (class "Default")
      (node (ref "C13") (pin "P$1") (pinfunction "P$1_P$1") (pintype "passive"))
      (node (ref "R8") (pin "P$2") (pinfunction "P$2_P$2") (pintype "passive"))
      (node (ref "R9") (pin "P$1") (pinfunction "P$1_P$1") (pintype "passive"))
      (node (ref "U1") (pin "31") (pinfunction "PA9_31") (pintype "bidirectional"))
    )
    (net (code "52") (name "/VTEMP_MOT") (class "Default")
      (node (ref "R7") (pin "P$1") (pinfunction "P$1_P$1") (pintype "passive"))
      (node (ref "TEMP2") (pin "P$1") (pinfunction "P$1_P$1") (pintype "bidirectional"))
      (node (ref "U1") (pin "30") (pinfunction "PA8_30") (pintype "bidirectional"))
    )
    (net (code "53") (name "GND") (class "Default")
      (node (ref "ABS") (pin "4") (pinfunction "4_4") (pintype "passive"))
      (node (ref "C1") (pin "P$2") (pinfunction "P$2_P$2") (pintype "passive"))
      (node (ref "C10") (pin "P$2") (pinfunction "P$2_P$2") (pintype "passive"))
      (node (ref "C11") (pin "P$2") (pinfunction "P$2_P$2") (pintype "passive"))
      (node (ref "C12") (pin "P$2") (pinfunction "P$2_P$2") (pintype "passive"))
      (node (ref "C13") (pin "P$2") (pinfunction "P$2_P$2") (pintype "passive"))
      (node (ref "C17") (pin "P$1") (pinfunction "P$1_P$1") (pintype "passive"))
      (node (ref "C18") (pin "P$1") (pinfunction "P$1_P$1") (pintype "passive"))
      (node (ref "C2") (pin "P$2") (pinfunction "P$2_P$2") (pintype "passive"))
      (node (ref "C21") (pin "P$2") (pinfunction "P$2_P$2") (pintype "passive"))
      (node (ref "C3") (pin "P$2") (pinfunction "P$2_P$2") (pintype "passive"))
      (node (ref "C4") (pin "P$2") (pinfunction "P$2_P$2") (pintype "passive"))
      (node (ref "C5") (pin "P$2") (pinfunction "P$2_P$2") (pintype "passive"))
      (node (ref "C6") (pin "P$2") (pinfunction "P$2_P$2") (pintype "passive"))
      (node (ref "C7") (pin "P$1") (pinfunction "P$1_P$1") (pintype "passive"))
      (node (ref "C8") (pin "P$2") (pinfunction "P$2_P$2") (pintype "passive"))
      (node (ref "C9") (pin "P$2") (pinfunction "P$2_P$2") (pintype "passive"))
      (node (ref "CAN1") (pin "3") (pinfunction "3_3") (pintype "passive"))
      (node (ref "CAN2") (pin "3") (pinfunction "3_3") (pintype "passive"))
      (node (ref "DG1") (pin "P$1") (pinfunction "P$1_P$1") (pintype "bidirectional"))
      (node (ref "DG2") (pin "P$1") (pinfunction "P$1_P$1") (pintype "bidirectional"))
      (node (ref "R6") (pin "P$1") (pinfunction "P$1_P$1") (pintype "passive"))
      (node (ref "R7") (pin "P$2") (pinfunction "P$2_P$2") (pintype "passive"))
      (node (ref "R9") (pin "P$2") (pinfunction "P$2_P$2") (pintype "passive"))
      (node (ref "SH4") (pin "2") (pinfunction "P$2_2") (pintype "bidirectional"))
      (node (ref "SWD") (pin "4") (pinfunction "4_4") (pintype "passive"))
      (node (ref "U1") (pin "29") (pinfunction "PC6_29") (pintype "bidirectional"))
      (node (ref "U1") (pin "49") (pinfunction "THERMALPAD_49") (pintype "bidirectional"))
      (node (ref "U2") (pin "2") (pinfunction "GND_2") (pintype "power_in"))
      (node (ref "U2") (pin "5") (pinfunction "SHDN_5") (pintype "input"))
      (node (ref "U2") (pin "8") (pinfunction "STB_8") (pintype "input"))
      (node (ref "U3") (pin "13") (pinfunction "GND_13") (pintype "bidirectional"))
      (node (ref "U3") (pin "5") (pinfunction "TEST_5") (pintype "bidirectional"))
      (node (ref "U4") (pin "27") (pinfunction "DGND_27") (pintype "bidirectional"))
      (node (ref "U4") (pin "35") (pinfunction "AGND_35") (pintype "bidirectional"))
    )
    (net (code "54") (name "Net-(D2-PadANODE)") (class "Default")
      (node (ref "D2") (pin "ANODE") (pinfunction "ANODE_ANODE") (pintype "power_in"))
      (node (ref "R2") (pin "P$2") (pinfunction "P$2_P$2") (pintype "passive"))
    )
    (net (code "55") (name "Net-(D3-PadANODE)") (class "Default")
      (node (ref "D3") (pin "ANODE") (pinfunction "ANODE_ANODE") (pintype "power_in"))
      (node (ref "R1") (pin "P$2") (pinfunction "P$2_P$2") (pintype "passive"))
    )
    (net (code "56") (name "Net-(U2-CANH)") (class "Default")
      (node (ref "CAN1") (pin "1") (pinfunction "1_1") (pintype "passive"))
      (node (ref "CAN2") (pin "1") (pinfunction "1_1") (pintype "passive"))
      (node (ref "U2") (pin "7") (pinfunction "CANH_7") (pintype "bidirectional"))
    )
    (net (code "57") (name "Net-(U2-CANL)") (class "Default")
      (node (ref "CAN1") (pin "2") (pinfunction "2_2") (pintype "passive"))
      (node (ref "CAN2") (pin "2") (pinfunction "2_2") (pintype "passive"))
      (node (ref "U2") (pin "6") (pinfunction "CANL_6") (pintype "bidirectional"))
    )
    (net (code "58") (name "Net-(U4-CB)") (class "Default")
      (node (ref "C20") (pin "P$1") (pinfunction "P$1_P$1") (pintype "passive"))
      (node (ref "U4") (pin "44") (pinfunction "CB_44") (pintype "bidirectional"))
    )
    (net (code "59") (name "Net-(U4-CPH)") (class "Default")
      (node (ref "C16") (pin "P$1") (pinfunction "P$1_P$1") (pintype "passive"))
      (node (ref "U4") (pin "4") (pinfunction "CPH_4") (pintype "bidirectional"))
    )
    (net (code "60") (name "Net-(U4-CPL)") (class "Default")
      (node (ref "C16") (pin "P$2") (pinfunction "P$2_P$2") (pintype "passive"))
      (node (ref "U4") (pin "3") (pinfunction "CPL_3") (pintype "bidirectional"))
    )
    (net (code "61") (name "Net-(U4-DVDD)") (class "Default")
      (node (ref "C17") (pin "P$2") (pinfunction "P$2_P$2") (pintype "passive"))
      (node (ref "U4") (pin "36") (pinfunction "DVDD_36") (pintype "bidirectional"))
    )
    (net (code "62") (name "Net-(U4-FB)") (class "Default")
      (node (ref "R11") (pin "P$2") (pinfunction "P$2_P$2") (pintype "passive"))
      (node (ref "R12") (pin "P$1") (pinfunction "P$1_P$1") (pintype "passive"))
      (node (ref "U4") (pin "1") (pinfunction "FB_1") (pintype "bidirectional"))
    )
    (net (code "63") (name "Net-(U4-SHDN)") (class "Default")
      (node (ref "R10") (pin "P$1") (pinfunction "P$1_P$1") (pintype "passive"))
      (node (ref "U4") (pin "48") (pinfunction "SHDN_48") (pintype "bidirectional"))
    )
    (net (code "64") (name "Net-(U4-SW)") (class "Default")
      (node (ref "C20") (pin "P$2") (pinfunction "P$2_P$2") (pintype "passive"))
      (node (ref "D1") (pin "CATHODE") (pinfunction "CATHODE_CATHODE") (pintype "bidirectional"))
      (node (ref "L1") (pin "2") (pinfunction "2_2") (pintype "passive"))
      (node (ref "U4") (pin "45") (pinfunction "SW_45") (pintype "bidirectional"))
    )
    (net (code "65") (name "Net-(U4-VCP)") (class "Default")
      (node (ref "C15") (pin "P$2") (pinfunction "P$2_P$2") (pintype "passive"))
      (node (ref "U4") (pin "5") (pinfunction "VCP_5") (pintype "bidirectional"))
    )
    (net (code "66") (name "V+") (class "Default")
      (node (ref "C14") (pin "P$1") (pinfunction "P$1_P$1") (pintype "passive"))
      (node (ref "C15") (pin "P$1") (pinfunction "P$1_P$1") (pintype "passive"))
      (node (ref "C19") (pin "P$1") (pinfunction "P$1_P$1") (pintype "passive"))
      (node (ref "C22") (pin "P$1") (pinfunction "P$1_P$1") (pintype "passive"))
      (node (ref "C23") (pin "P$1") (pinfunction "P$1_P$1") (pintype "passive"))
      (node (ref "C24") (pin "P$1") (pinfunction "P$1_P$1") (pintype "passive"))
      (node (ref "C25") (pin "P$1") (pinfunction "P$1_P$1") (pintype "passive"))
      (node (ref "C26") (pin "P$1") (pinfunction "P$1_P$1") (pintype "passive"))
      (node (ref "C27") (pin "P$1") (pinfunction "P$1_P$1") (pintype "passive"))
      (node (ref "C28") (pin "P$1") (pinfunction "P$1_P$1") (pintype "passive"))
      (node (ref "C29") (pin "P$1") (pinfunction "P$1_P$1") (pintype "passive"))
      (node (ref "C30") (pin "P$1") (pinfunction "P$1_P$1") (pintype "passive"))
      (node (ref "C31") (pin "P$1") (pinfunction "P$1_P$1") (pintype "passive"))
      (node (ref "C32") (pin "P$1") (pinfunction "P$1_P$1") (pintype "passive"))
      (node (ref "C33") (pin "P$1") (pinfunction "P$1_P$1") (pintype "passive"))
      (node (ref "C34") (pin "P$1") (pinfunction "P$1_P$1") (pintype "passive"))
      (node (ref "C35") (pin "P$1") (pinfunction "P$1_P$1") (pintype "passive"))
      (node (ref "C36") (pin "P$1") (pinfunction "P$1_P$1") (pintype "passive"))
      (node (ref "C37") (pin "P$1") (pinfunction "P$1_P$1") (pintype "passive"))
      (node (ref "J1") (pin "1") (pinfunction "1_1") (pintype "passive"))
      (node (ref "J2") (pin "1") (pinfunction "1_1") (pintype "passive"))
      (node (ref "Q1") (pin "5") (pinfunction "D_5") (pintype "passive"))
      (node (ref "Q1") (pin "6") (pinfunction "D_6") (pintype "passive"))
      (node (ref "Q1") (pin "7") (pinfunction "D_7") (pintype "passive"))
      (node (ref "Q1") (pin "8") (pinfunction "D_8") (pintype "passive"))
      (node (ref "Q1") (pin "PAD") (pinfunction "D_PAD") (pintype "passive"))
      (node (ref "Q3") (pin "5") (pinfunction "D_5") (pintype "passive"))
      (node (ref "Q3") (pin "6") (pinfunction "D_6") (pintype "passive"))
      (node (ref "Q3") (pin "7") (pinfunction "D_7") (pintype "passive"))
      (node (ref "Q3") (pin "8") (pinfunction "D_8") (pintype "passive"))
      (node (ref "Q3") (pin "PAD") (pinfunction "D_PAD") (pintype "passive"))
      (node (ref "Q5") (pin "5") (pinfunction "D_5") (pintype "passive"))
      (node (ref "Q5") (pin "6") (pinfunction "D_6") (pintype "passive"))
      (node (ref "Q5") (pin "7") (pinfunction "D_7") (pintype "passive"))
      (node (ref "Q5") (pin "8") (pinfunction "D_8") (pintype "passive"))
      (node (ref "Q5") (pin "PAD") (pinfunction "D_PAD") (pintype "passive"))
      (node (ref "R10") (pin "P$2") (pinfunction "P$2_P$2") (pintype "passive"))
      (node (ref "R5") (pin "P$2") (pinfunction "P$2_P$2") (pintype "passive"))
      (node (ref "U4") (pin "47") (pinfunction "VIN_47") (pintype "bidirectional"))
      (node (ref "U4") (pin "6") (pinfunction "VM_6") (pintype "bidirectional"))
      (node (ref "U4") (pin "7") (pinfunction "VDRAIN_7") (pintype "bidirectional"))
    )
    (net (code "67") (name "V-") (class "Default")
      (node (ref "C14") (pin "P$2") (pinfunction "P$2_P$2") (pintype "passive"))
      (node (ref "C19") (pin "P$2") (pinfunction "P$2_P$2") (pintype "passive"))
      (node (ref "C22") (pin "P$2") (pinfunction "P$2_P$2") (pintype "passive"))
      (node (ref "C23") (pin "P$2") (pinfunction "P$2_P$2") (pintype "passive"))
      (node (ref "C24") (pin "P$2") (pinfunction "P$2_P$2") (pintype "passive"))
      (node (ref "C25") (pin "P$2") (pinfunction "P$2_P$2") (pintype "passive"))
      (node (ref "C26") (pin "P$2") (pinfunction "P$2_P$2") (pintype "passive"))
      (node (ref "C27") (pin "P$2") (pinfunction "P$2_P$2") (pintype "passive"))
      (node (ref "C28") (pin "P$2") (pinfunction "P$2_P$2") (pintype "passive"))
      (node (ref "C29") (pin "P$2") (pinfunction "P$2_P$2") (pintype "passive"))
      (node (ref "C30") (pin "P$2") (pinfunction "P$2_P$2") (pintype "passive"))
      (node (ref "C31") (pin "P$2") (pinfunction "P$2_P$2") (pintype "passive"))
      (node (ref "C32") (pin "P$2") (pinfunction "P$2_P$2") (pintype "passive"))
      (node (ref "C33") (pin "P$2") (pinfunction "P$2_P$2") (pintype "passive"))
      (node (ref "C34") (pin "P$2") (pinfunction "P$2_P$2") (pintype "passive"))
      (node (ref "C35") (pin "P$2") (pinfunction "P$2_P$2") (pintype "passive"))
      (node (ref "C36") (pin "P$2") (pinfunction "P$2_P$2") (pintype "passive"))
      (node (ref "C37") (pin "P$2") (pinfunction "P$2_P$2") (pintype "passive"))
      (node (ref "D1") (pin "ANODE") (pinfunction "ANODE_ANODE") (pintype "bidirectional"))
      (node (ref "J1") (pin "2") (pinfunction "2_2") (pintype "passive"))
      (node (ref "J2") (pin "2") (pinfunction "2_2") (pintype "passive"))
      (node (ref "R12") (pin "P$2") (pinfunction "P$2_P$2") (pintype "passive"))
      (node (ref "RA") (pin "1") (pinfunction "1_1") (pintype "passive"))
      (node (ref "RB") (pin "1") (pinfunction "1_1") (pintype "passive"))
      (node (ref "RC") (pin "1") (pinfunction "1_1") (pintype "passive"))
      (node (ref "SH1") (pin "2") (pinfunction "P$2_2") (pintype "bidirectional"))
      (node (ref "SH2") (pin "2") (pinfunction "P$2_2") (pintype "bidirectional"))
      (node (ref "SH3") (pin "2") (pinfunction "P$2_2") (pintype "bidirectional"))
      (node (ref "SH4") (pin "1") (pinfunction "P$1_1") (pintype "bidirectional"))
      (node (ref "U4") (pin "2") (pinfunction "PGND_2") (pintype "bidirectional"))
      (node (ref "U4") (pin "43") (pinfunction "BGND_43") (pintype "bidirectional"))
      (node (ref "U4") (pin "P1") (pinfunction "PAD_P1") (pintype "bidirectional"))
      (node (ref "U4") (pin "P10") (pinfunction "PAD_P10") (pintype "bidirectional"))
      (node (ref "U4") (pin "P11") (pinfunction "PAD_P11") (pintype "bidirectional"))
      (node (ref "U4") (pin "P12") (pinfunction "PAD_P12") (pintype "bidirectional"))
      (node (ref "U4") (pin "P13") (pinfunction "PAD_P13") (pintype "bidirectional"))
      (node (ref "U4") (pin "P14") (pinfunction "PAD_P14") (pintype "bidirectional"))
      (node (ref "U4") (pin "P15") (pinfunction "PAD_P15") (pintype "bidirectional"))
      (node (ref "U4") (pin "P16") (pinfunction "PAD_P16") (pintype "bidirectional"))
      (node (ref "U4") (pin "P17") (pinfunction "PAD_P17") (pintype "bidirectional"))
      (node (ref "U4") (pin "P18") (pinfunction "PAD_P18") (pintype "bidirectional"))
      (node (ref "U4") (pin "P19") (pinfunction "PAD_P19") (pintype "bidirectional"))
      (node (ref "U4") (pin "P2") (pinfunction "PAD_P2") (pintype "bidirectional"))
      (node (ref "U4") (pin "P20") (pinfunction "PAD_P20") (pintype "bidirectional"))
      (node (ref "U4") (pin "P21") (pinfunction "PAD_P21") (pintype "bidirectional"))
      (node (ref "U4") (pin "P22") (pinfunction "PAD_P22") (pintype "bidirectional"))
      (node (ref "U4") (pin "P23") (pinfunction "PAD_P23") (pintype "bidirectional"))
      (node (ref "U4") (pin "P24") (pinfunction "PAD_P24") (pintype "bidirectional"))
      (node (ref "U4") (pin "P25") (pinfunction "PAD_P25") (pintype "bidirectional"))
      (node (ref "U4") (pin "P3") (pinfunction "PAD_P3") (pintype "bidirectional"))
      (node (ref "U4") (pin "P4") (pinfunction "PAD_P4") (pintype "bidirectional"))
      (node (ref "U4") (pin "P5") (pinfunction "PAD_P5") (pintype "bidirectional"))
      (node (ref "U4") (pin "P6") (pinfunction "PAD_P6") (pintype "bidirectional"))
      (node (ref "U4") (pin "P7") (pinfunction "PAD_P7") (pintype "bidirectional"))
      (node (ref "U4") (pin "P8") (pinfunction "PAD_P8") (pintype "bidirectional"))
      (node (ref "U4") (pin "P9") (pinfunction "PAD_P9") (pintype "bidirectional"))
      (node (ref "U4") (pin "PAD") (pinfunction "PAD_PAD") (pintype "bidirectional"))
    )
    (net (code "68") (name "unconnected-(SWD-Pad1)") (class "Default")
      (node (ref "SWD") (pin "1") (pinfunction "1_1") (pintype "passive"))
    )
    (net (code "69") (name "unconnected-(U1-PA10-Pad32)") (class "Default")
      (node (ref "U1") (pin "32") (pinfunction "PA10_32") (pintype "bidirectional"))
    )
    (net (code "70") (name "unconnected-(U1-PA15-Pad38)") (class "Default")
      (node (ref "U1") (pin "38") (pinfunction "PA15_38") (pintype "bidirectional"))
    )
    (net (code "71") (name "unconnected-(U1-PB3-Pad41)") (class "Default")
      (node (ref "U1") (pin "41") (pinfunction "PB3_41") (pintype "bidirectional"))
    )
    (net (code "72") (name "unconnected-(U1-PB10-Pad22)") (class "Default")
      (node (ref "U1") (pin "22") (pinfunction "PB10_22") (pintype "bidirectional"))
    )
    (net (code "73") (name "unconnected-(U1-PC13-Pad2)") (class "Default")
      (node (ref "U1") (pin "2") (pinfunction "PC13_2") (pintype "bidirectional"))
    )
    (net (code "74") (name "unconnected-(U3-I-Pad14)") (class "Default")
      (node (ref "U3") (pin "14") (pinfunction "I_14") (pintype "bidirectional"))
    )
    (net (code "75") (name "unconnected-(U3-PWM-Pad8)") (class "Default")
      (node (ref "U3") (pin "8") (pinfunction "PWM_8") (pintype "bidirectional"))
    )
    (net (code "76") (name "unconnected-(U3-VDD5V-Pad11)") (class "Default")
      (node (ref "U3") (pin "11") (pinfunction "VDD5V_11") (pintype "bidirectional"))
    )
    (net (code "77") (name "unconnected-(U4-CAL-Pad34)") (class "Default")
      (node (ref "U4") (pin "34") (pinfunction "CAL_34") (pintype "bidirectional"))
    )
  )
)
